# frontplatine_v0_2_140202.net
KiCad netlist of a schematic drawn in EAGLE
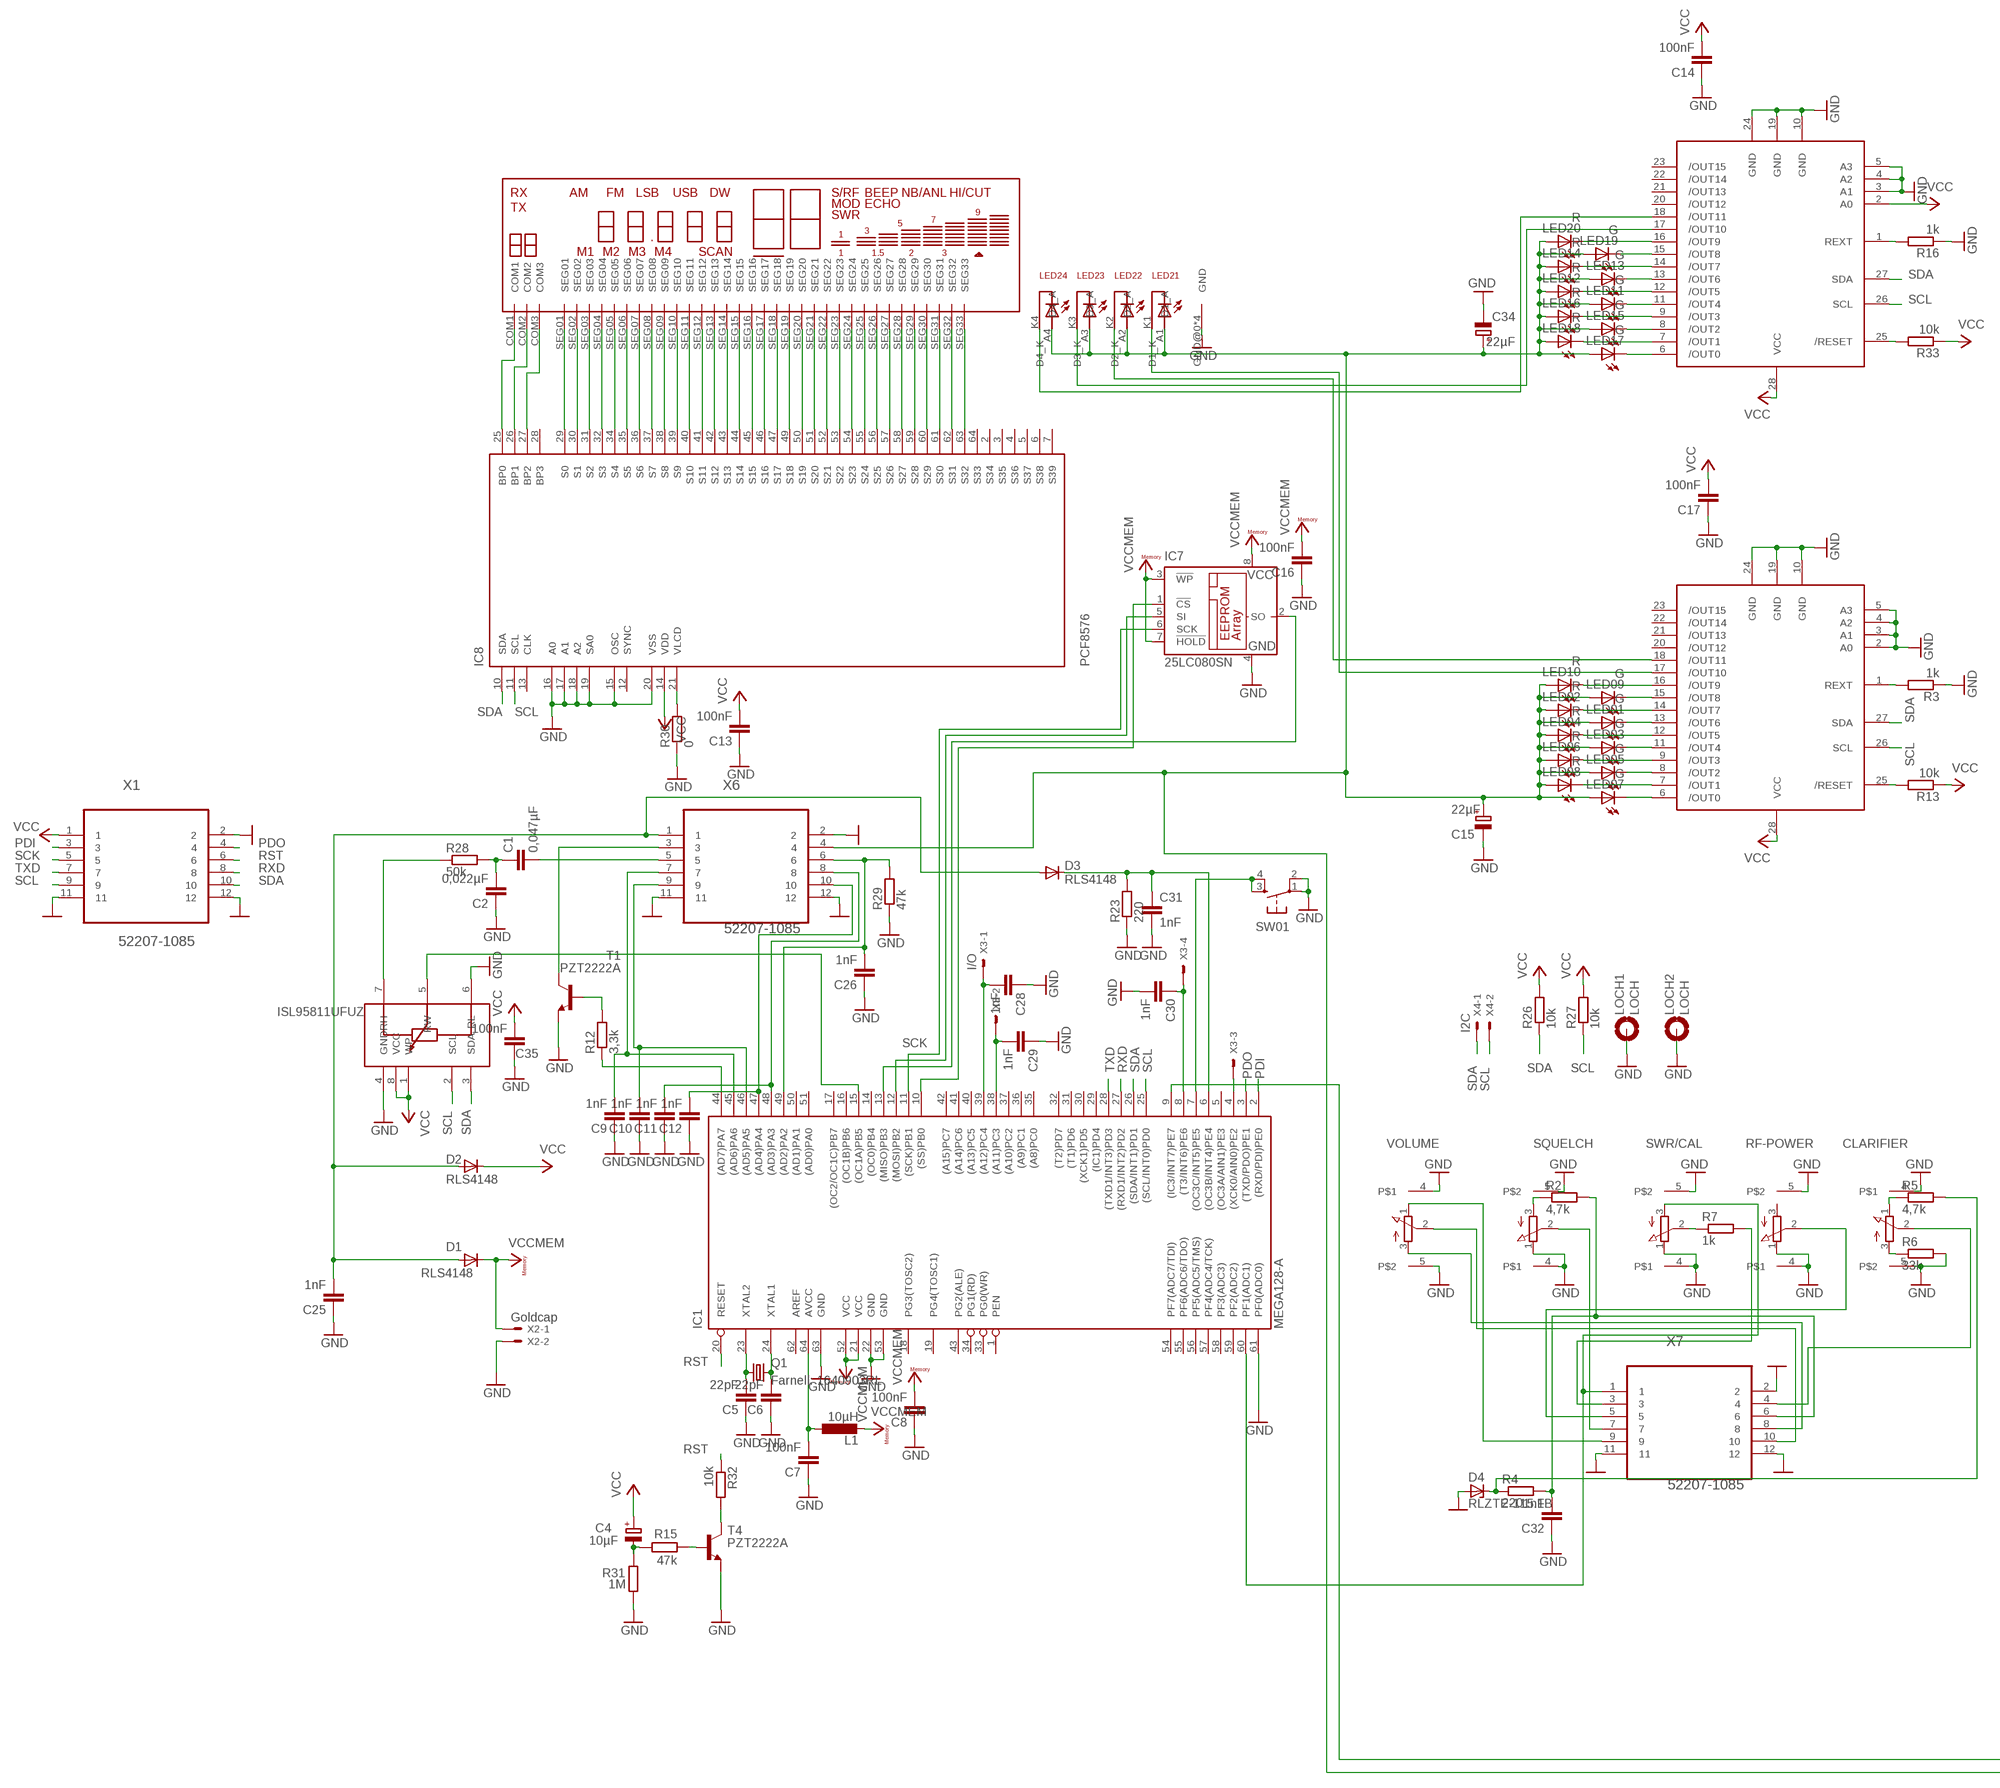
[diagram p0: schematic, sheet 1, part 1 of 2]
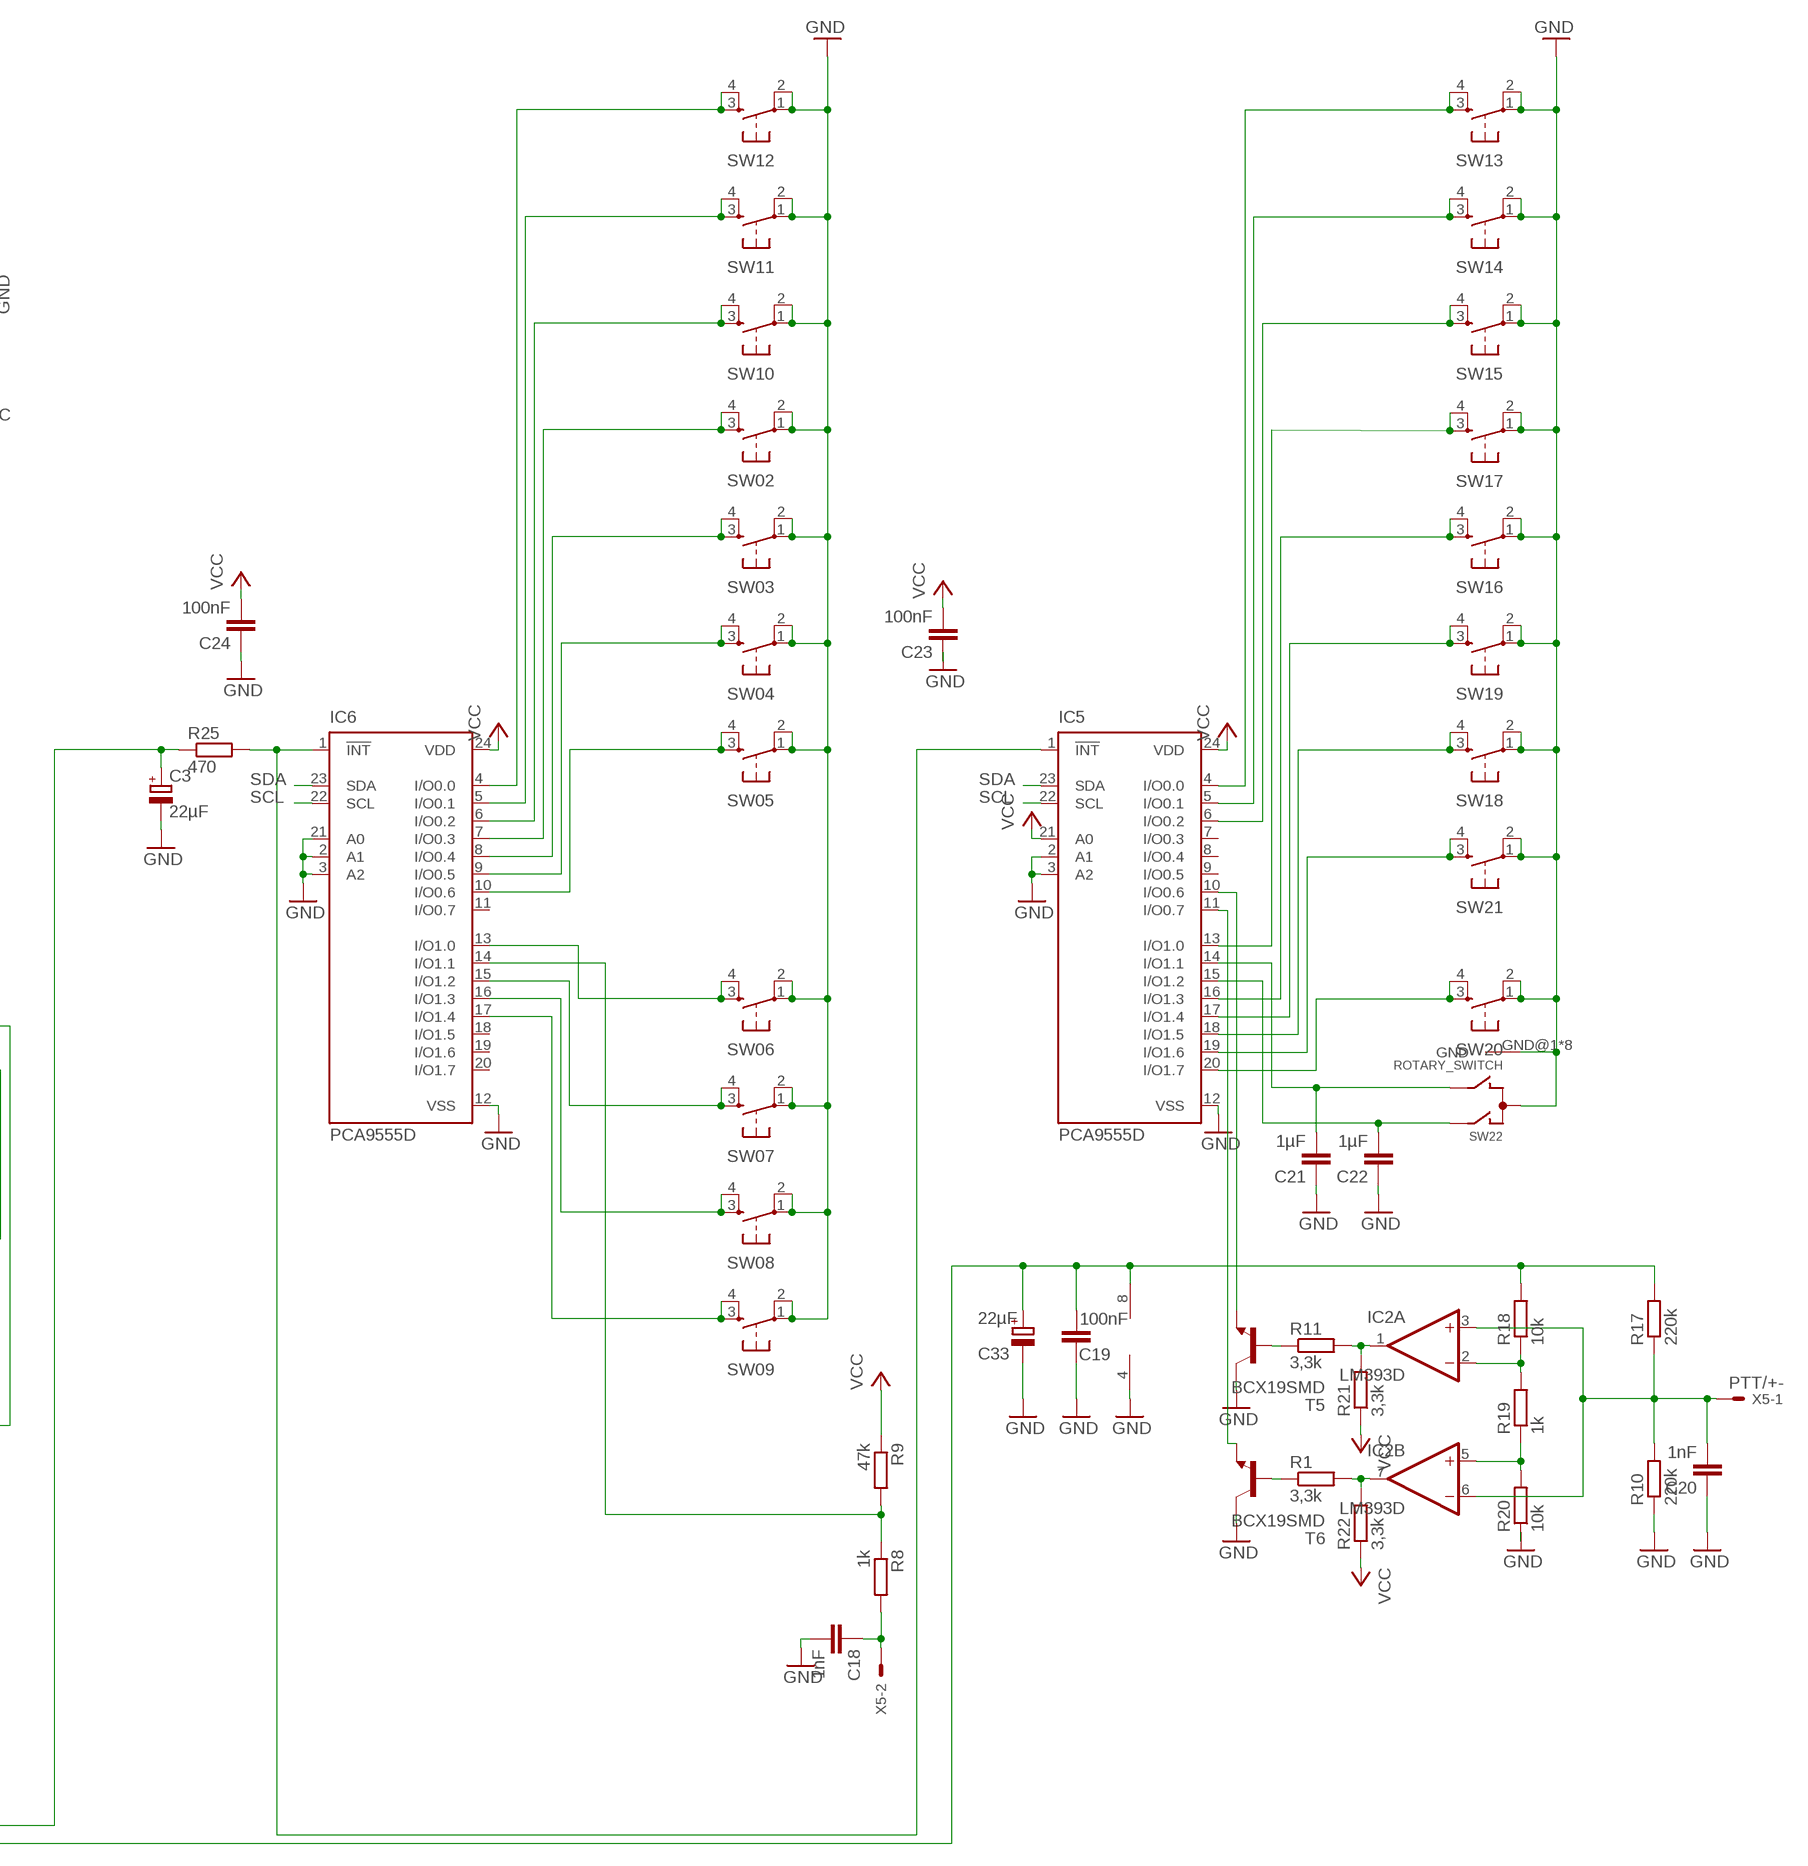
[diagram p1: schematic, sheet 1, part 2 of 2]

(export (version "E")
  (design (tool "Eeschema 10.0.6"))
  (components
    (comp (ref "C1")
      (value "0,047µF")
      (footprint "eagle-import:C1206")
      (libsource (lib "eagle-import") (part "C-EUC1206"))
    )
    (comp (ref "C2")
      (value "0,022µF")
      (footprint "eagle-import:C1206")
      (libsource (lib "eagle-import") (part "resistor_C-EUC1206"))
    )
    (comp (ref "C3")
      (value "22µF")
      (footprint "eagle-import:CT3216")
      (libsource (lib "eagle-import") (part "CPOL-EUCT3216"))
    )
    (comp (ref "C4")
      (value "10µF")
      (footprint "eagle-import:CT3216")
      (libsource (lib "eagle-import") (part "CPOL-EUCT3216"))
    )
    (comp (ref "C5")
      (value "22pF")
      (footprint "eagle-import:C1206")
      (libsource (lib "eagle-import") (part "resistor_C-EUC1206"))
    )
    (comp (ref "C6")
      (value "22pF")
      (footprint "eagle-import:C1206")
      (libsource (lib "eagle-import") (part "resistor_C-EUC1206"))
    )
    (comp (ref "C7")
      (value "100nF")
      (footprint "eagle-import:C1206")
      (libsource (lib "eagle-import") (part "resistor_C-EUC1206"))
    )
    (comp (ref "C8")
      (value "100nF")
      (footprint "eagle-import:C1206")
      (libsource (lib "eagle-import") (part "resistor_C-EUC1206"))
    )
    (comp (ref "C9")
      (value "1nF")
      (footprint "eagle-import:C1206")
      (libsource (lib "eagle-import") (part "resistor_C-EUC1206"))
    )
    (comp (ref "C10")
      (value "1nF")
      (footprint "eagle-import:C1206")
      (libsource (lib "eagle-import") (part "resistor_C-EUC1206"))
    )
    (comp (ref "C11")
      (value "1nF")
      (footprint "eagle-import:C1206")
      (libsource (lib "eagle-import") (part "resistor_C-EUC1206"))
    )
    (comp (ref "C12")
      (value "1nF")
      (footprint "eagle-import:C1206")
      (libsource (lib "eagle-import") (part "resistor_C-EUC1206"))
    )
    (comp (ref "C13")
      (value "100nF")
      (footprint "eagle-import:C1206")
      (libsource (lib "eagle-import") (part "resistor_C-EUC1206"))
    )
    (comp (ref "C14")
      (value "100nF")
      (footprint "eagle-import:C1206")
      (libsource (lib "eagle-import") (part "resistor_C-EUC1206"))
    )
    (comp (ref "C15")
      (value "22µF")
      (footprint "eagle-import:CT3216")
      (libsource (lib "eagle-import") (part "CPOL-EUCT3216"))
    )
    (comp (ref "C16")
      (value "100nF")
      (footprint "eagle-import:C1206")
      (libsource (lib "eagle-import") (part "resistor_C-EUC1206"))
    )
    (comp (ref "C17")
      (value "100nF")
      (footprint "eagle-import:C1206")
      (libsource (lib "eagle-import") (part "resistor_C-EUC1206"))
    )
    (comp (ref "C18")
      (value "1nF")
      (footprint "eagle-import:C1206")
      (libsource (lib "eagle-import") (part "resistor_C-EUC1206"))
    )
    (comp (ref "C19")
      (value "100nF")
      (footprint "eagle-import:C1206")
      (libsource (lib "eagle-import") (part "resistor_C-EUC1206"))
    )
    (comp (ref "C20")
      (value "1nF")
      (footprint "eagle-import:C1206")
      (libsource (lib "eagle-import") (part "resistor_C-EUC1206"))
    )
    (comp (ref "C21")
      (value "1µF")
      (footprint "eagle-import:C1206")
      (libsource (lib "eagle-import") (part "resistor_C-EUC1206"))
    )
    (comp (ref "C22")
      (value "1µF")
      (footprint "eagle-import:C1206")
      (libsource (lib "eagle-import") (part "resistor_C-EUC1206"))
    )
    (comp (ref "C23")
      (value "100nF")
      (footprint "eagle-import:C1206")
      (libsource (lib "eagle-import") (part "resistor_C-EUC1206"))
    )
    (comp (ref "C24")
      (value "100nF")
      (footprint "eagle-import:C1206")
      (libsource (lib "eagle-import") (part "resistor_C-EUC1206"))
    )
    (comp (ref "C25")
      (value "1nF")
      (footprint "eagle-import:C1206")
      (libsource (lib "eagle-import") (part "resistor_C-EUC1206"))
    )
    (comp (ref "C26")
      (value "1nF")
      (footprint "eagle-import:C1206")
      (libsource (lib "eagle-import") (part "resistor_C-EUC1206"))
    )
    (comp (ref "C28")
      (value "1nF")
      (footprint "eagle-import:C1206")
      (libsource (lib "eagle-import") (part "resistor_C-EUC1206"))
    )
    (comp (ref "C29")
      (value "1nF")
      (footprint "eagle-import:C1206")
      (libsource (lib "eagle-import") (part "resistor_C-EUC1206"))
    )
    (comp (ref "C30")
      (value "1nF")
      (footprint "eagle-import:C1206")
      (libsource (lib "eagle-import") (part "resistor_C-EUC1206"))
    )
    (comp (ref "C31")
      (value "1nF")
      (footprint "eagle-import:C1206")
      (libsource (lib "eagle-import") (part "resistor_C-EUC1206"))
    )
    (comp (ref "C32")
      (value "1nF")
      (footprint "eagle-import:C1206")
      (libsource (lib "eagle-import") (part "resistor_C-EUC1206"))
    )
    (comp (ref "C33")
      (value "22µF")
      (footprint "eagle-import:CT3216")
      (libsource (lib "eagle-import") (part "CPOL-EUCT3216"))
    )
    (comp (ref "C34")
      (value "22µF")
      (footprint "eagle-import:CT3216")
      (libsource (lib "eagle-import") (part "CPOL-EUCT3216"))
    )
    (comp (ref "C35")
      (value "100nF")
      (footprint "eagle-import:C1206")
      (libsource (lib "eagle-import") (part "resistor_C-EUC1206"))
    )
    (comp (ref "CLARIFIER")
      (value "POTI")
      (footprint "eagle-import:POTI")
      (libsource (lib "eagle-import") (part "POTI"))
    )
    (comp (ref "D1")
      (value "RLS4148")
      (footprint "eagle-import:SOD80C")
      (libsource (lib "eagle-import") (part "DIODE-SOD80C"))
    )
    (comp (ref "D2")
      (value "RLS4148")
      (footprint "eagle-import:SOD80C")
      (libsource (lib "eagle-import") (part "DIODE-SOD80C"))
    )
    (comp (ref "D3")
      (value "RLS4148")
      (footprint "eagle-import:SOD80C")
      (libsource (lib "eagle-import") (part "DIODE-SOD80C"))
    )
    (comp (ref "D4")
      (value "RLZTE-115.1B")
      (footprint "eagle-import:SOD80C")
      (libsource (lib "eagle-import") (part "ZENER-DIODESOD80C"))
    )
    (comp (ref "DISPLAY1")
      (value "DISPLAY")
      (footprint "eagle-import:DISPLAY")
      (libsource (lib "eagle-import") (part "DISPLAY"))
    )
    (comp (ref "IC1")
      (value "MEGA128-A")
      (footprint "eagle-import:TQFP64")
      (fields (field (name "MPN") "ATMEGA128-16AU"))
      (libsource (lib "eagle-import") (part "MEGA128-A"))
    )
    (comp (ref "IC2")
      (value "LM393D")
      (footprint "eagle-import:SO08")
      (libsource (lib "eagle-import") (part "LM393D"))
    )
    (comp (ref "IC3")
      (value "TLC59116")
      (footprint "eagle-import:TSSOP28")
      (libsource (lib "eagle-import") (part "TLC59116"))
    )
    (comp (ref "IC4")
      (value "TLC59116")
      (footprint "eagle-import:TSSOP28")
      (libsource (lib "eagle-import") (part "TLC59116"))
    )
    (comp (ref "IC5")
      (value "PCA9555D")
      (footprint "eagle-import:SO24")
      (fields (field (name "MPN") "PCA9555DW"))
      (libsource (lib "eagle-import") (part "PCA9555D"))
    )
    (comp (ref "IC6")
      (value "PCA9555D")
      (footprint "eagle-import:SO24")
      (fields (field (name "MPN") "PCA9555DW"))
      (libsource (lib "eagle-import") (part "PCA9555D"))
    )
    (comp (ref "IC7")
      (value "25LC080SN")
      (footprint "eagle-import:SO-08")
      (fields
        (field (name "MF") "MICROCHIP")
        (field (name "MPN") "25LC080/SN")
        (field (name "MPN_1") "25LC080/SN")
        (field (name "OC_FARNELL") "1137302")
        (field (name "OC_NEWARK") "96K4092")
      )
      (libsource (lib "eagle-import") (part "25SNLC080"))
    )
    (comp (ref "IC8")
      (value "PCF8576")
      (footprint "eagle-import:LQFP-ST-64-2")
      (libsource (lib "eagle-import") (part "PCF8576"))
    )
    (comp (ref "IC9")
      (value "ISL95811UFUZ")
      (footprint "eagle-import:MSOP8")
      (libsource (lib "eagle-import") (part "ISL95811UFUZ"))
    )
    (comp (ref "L1")
      (value "10µH")
      (footprint "eagle-import:L1812")
      (libsource (lib "eagle-import") (part "L-EUL1812"))
    )
    (comp (ref "LED01")
      (value "G")
      (footprint "eagle-import:CHIPLED_1206")
      (libsource (lib "eagle-import") (part "LEDCHIPLED_1206"))
    )
    (comp (ref "LED02")
      (value "R")
      (footprint "eagle-import:CHIPLED_1206")
      (libsource (lib "eagle-import") (part "LEDCHIPLED_1206"))
    )
    (comp (ref "LED03")
      (value "G")
      (footprint "eagle-import:CHIPLED_1206")
      (libsource (lib "eagle-import") (part "LEDCHIPLED_1206"))
    )
    (comp (ref "LED04")
      (value "R")
      (footprint "eagle-import:CHIPLED_1206")
      (libsource (lib "eagle-import") (part "LEDCHIPLED_1206"))
    )
    (comp (ref "LED05")
      (value "G")
      (footprint "eagle-import:CHIPLED_1206")
      (libsource (lib "eagle-import") (part "LEDCHIPLED_1206"))
    )
    (comp (ref "LED06")
      (value "R")
      (footprint "eagle-import:CHIPLED_1206")
      (libsource (lib "eagle-import") (part "LEDCHIPLED_1206"))
    )
    (comp (ref "LED07")
      (value "G")
      (footprint "eagle-import:CHIPLED_1206")
      (libsource (lib "eagle-import") (part "LEDCHIPLED_1206"))
    )
    (comp (ref "LED08")
      (value "R")
      (footprint "eagle-import:CHIPLED_1206")
      (libsource (lib "eagle-import") (part "LEDCHIPLED_1206"))
    )
    (comp (ref "LED09")
      (value "G")
      (footprint "eagle-import:CHIPLED_1206")
      (libsource (lib "eagle-import") (part "LEDCHIPLED_1206"))
    )
    (comp (ref "LED10")
      (value "R")
      (footprint "eagle-import:CHIPLED_1206")
      (libsource (lib "eagle-import") (part "LEDCHIPLED_1206"))
    )
    (comp (ref "LED11")
      (value "G")
      (footprint "eagle-import:CHIPLED_1206")
      (libsource (lib "eagle-import") (part "LEDCHIPLED_1206"))
    )
    (comp (ref "LED12")
      (value "R")
      (footprint "eagle-import:CHIPLED_1206")
      (libsource (lib "eagle-import") (part "LEDCHIPLED_1206"))
    )
    (comp (ref "LED13")
      (value "G")
      (footprint "eagle-import:CHIPLED_1206")
      (libsource (lib "eagle-import") (part "LEDCHIPLED_1206"))
    )
    (comp (ref "LED14")
      (value "R")
      (footprint "eagle-import:CHIPLED_1206")
      (libsource (lib "eagle-import") (part "LEDCHIPLED_1206"))
    )
    (comp (ref "LED15")
      (value "G")
      (footprint "eagle-import:CHIPLED_1206")
      (libsource (lib "eagle-import") (part "LEDCHIPLED_1206"))
    )
    (comp (ref "LED16")
      (value "R")
      (footprint "eagle-import:CHIPLED_1206")
      (libsource (lib "eagle-import") (part "LEDCHIPLED_1206"))
    )
    (comp (ref "LED17")
      (value "G")
      (footprint "eagle-import:CHIPLED_1206")
      (libsource (lib "eagle-import") (part "LEDCHIPLED_1206"))
    )
    (comp (ref "LED18")
      (value "R")
      (footprint "eagle-import:CHIPLED_1206")
      (libsource (lib "eagle-import") (part "LEDCHIPLED_1206"))
    )
    (comp (ref "LED19")
      (value "G")
      (footprint "eagle-import:CHIPLED_1206")
      (libsource (lib "eagle-import") (part "LEDCHIPLED_1206"))
    )
    (comp (ref "LED20")
      (value "R")
      (footprint "eagle-import:CHIPLED_1206")
      (libsource (lib "eagle-import") (part "LEDCHIPLED_1206"))
    )
    (comp (ref "LOCH1")
      (value "LOCH")
      (footprint "eagle-import:LOCH")
      (libsource (lib "eagle-import") (part "LOCH"))
    )
    (comp (ref "LOCH2")
      (value "LOCH")
      (footprint "eagle-import:LOCH")
      (libsource (lib "eagle-import") (part "LOCH"))
    )
    (comp (ref "Q1")
      (value "Farnell: 1640903RL")
      (footprint "eagle-import:HC49UP")
      (libsource (lib "eagle-import") (part "CRYSTALHC49UP"))
    )
    (comp (ref "R1")
      (value "3,3k")
      (footprint "eagle-import:R1206")
      (libsource (lib "eagle-import") (part "resistor_R-EU_R1206"))
    )
    (comp (ref "R2")
      (value "4,7k")
      (footprint "eagle-import:R1206")
      (libsource (lib "eagle-import") (part "resistor_R-EU_R1206"))
    )
    (comp (ref "R3")
      (value "1k")
      (footprint "eagle-import:R1206")
      (libsource (lib "eagle-import") (part "R-EU_R1206"))
    )
    (comp (ref "R4")
      (value "220")
      (footprint "eagle-import:R1206")
      (libsource (lib "eagle-import") (part "resistor_R-EU_R1206"))
    )
    (comp (ref "R5")
      (value "4,7k")
      (footprint "eagle-import:R1206")
      (libsource (lib "eagle-import") (part "resistor_R-EU_R1206"))
    )
    (comp (ref "R6")
      (value "33k")
      (footprint "eagle-import:R1206")
      (libsource (lib "eagle-import") (part "resistor_R-EU_R1206"))
    )
    (comp (ref "R7")
      (value "1k")
      (footprint "eagle-import:R1206")
      (libsource (lib "eagle-import") (part "resistor_R-EU_R1206"))
    )
    (comp (ref "R8")
      (value "1k")
      (footprint "eagle-import:R1206")
      (libsource (lib "eagle-import") (part "resistor_R-EU_R1206"))
    )
    (comp (ref "R9")
      (value "47k")
      (footprint "eagle-import:R1206")
      (libsource (lib "eagle-import") (part "resistor_R-EU_R1206"))
    )
    (comp (ref "R10")
      (value "220k")
      (footprint "eagle-import:R1206")
      (libsource (lib "eagle-import") (part "resistor_R-EU_R1206"))
    )
    (comp (ref "R11")
      (value "3,3k")
      (footprint "eagle-import:R1206")
      (libsource (lib "eagle-import") (part "resistor_R-EU_R1206"))
    )
    (comp (ref "R12")
      (value "3,3k")
      (footprint "eagle-import:R1206")
      (libsource (lib "eagle-import") (part "resistor_R-EU_R1206"))
    )
    (comp (ref "R13")
      (value "10k")
      (footprint "eagle-import:R1206")
      (libsource (lib "eagle-import") (part "resistor_R-EU_R1206"))
    )
    (comp (ref "R15")
      (value "47k")
      (footprint "eagle-import:R1206")
      (libsource (lib "eagle-import") (part "resistor_R-EU_R1206"))
    )
    (comp (ref "R16")
      (value "1k")
      (footprint "eagle-import:R1206")
      (libsource (lib "eagle-import") (part "R-EU_R1206"))
    )
    (comp (ref "R17")
      (value "220k")
      (footprint "eagle-import:R1206")
      (libsource (lib "eagle-import") (part "resistor_R-EU_R1206"))
    )
    (comp (ref "R18")
      (value "10k")
      (footprint "eagle-import:R1206")
      (libsource (lib "eagle-import") (part "resistor_R-EU_R1206"))
    )
    (comp (ref "R19")
      (value "1k")
      (footprint "eagle-import:R1206")
      (libsource (lib "eagle-import") (part "resistor_R-EU_R1206"))
    )
    (comp (ref "R20")
      (value "10k")
      (footprint "eagle-import:R1206")
      (libsource (lib "eagle-import") (part "resistor_R-EU_R1206"))
    )
    (comp (ref "R21")
      (value "3,3k")
      (footprint "eagle-import:R1206")
      (libsource (lib "eagle-import") (part "resistor_R-EU_R1206"))
    )
    (comp (ref "R22")
      (value "3,3k")
      (footprint "eagle-import:R1206")
      (libsource (lib "eagle-import") (part "resistor_R-EU_R1206"))
    )
    (comp (ref "R23")
      (value "220")
      (footprint "eagle-import:R1206")
      (libsource (lib "eagle-import") (part "resistor_R-EU_R1206"))
    )
    (comp (ref "R25")
      (value "470")
      (footprint "eagle-import:R1206")
      (libsource (lib "eagle-import") (part "resistor_R-EU_R1206"))
    )
    (comp (ref "R26")
      (value "10k")
      (footprint "eagle-import:R1206")
      (libsource (lib "eagle-import") (part "resistor_R-EU_R1206"))
    )
    (comp (ref "R27")
      (value "10k")
      (footprint "eagle-import:R1206")
      (libsource (lib "eagle-import") (part "resistor_R-EU_R1206"))
    )
    (comp (ref "R28")
      (value "50k")
      (footprint "eagle-import:R1206")
      (libsource (lib "eagle-import") (part "resistor_R-EU_R1206"))
    )
    (comp (ref "R29")
      (value "47k")
      (footprint "eagle-import:R1206")
      (libsource (lib "eagle-import") (part "resistor_R-EU_R1206"))
    )
    (comp (ref "R30")
      (value "0")
      (footprint "eagle-import:R1206")
      (libsource (lib "eagle-import") (part "resistor_R-EU_R1206"))
    )
    (comp (ref "R31")
      (value "1M")
      (footprint "eagle-import:R1206")
      (libsource (lib "eagle-import") (part "resistor_R-EU_R1206"))
    )
    (comp (ref "R32")
      (value "10k")
      (footprint "eagle-import:R1206")
      (libsource (lib "eagle-import") (part "resistor_R-EU_R1206"))
    )
    (comp (ref "R33")
      (value "10k")
      (footprint "eagle-import:R1206")
      (libsource (lib "eagle-import") (part "resistor_R-EU_R1206"))
    )
    (comp (ref "RF-POWER")
      (value "POTI")
      (footprint "eagle-import:POTI")
      (libsource (lib "eagle-import") (part "POTI"))
    )
    (comp (ref "SQUELCH")
      (value "POTI")
      (footprint "eagle-import:POTI")
      (libsource (lib "eagle-import") (part "POTI"))
    )
    (comp (ref "SW01")
      (value "TASTER")
      (footprint "eagle-import:TASTER")
      (libsource (lib "eagle-import") (part "TASTER"))
    )
    (comp (ref "SW02")
      (value "TASTER")
      (footprint "eagle-import:TASTER")
      (libsource (lib "eagle-import") (part "TASTER"))
    )
    (comp (ref "SW03")
      (value "TASTER")
      (footprint "eagle-import:TASTER")
      (libsource (lib "eagle-import") (part "TASTER"))
    )
    (comp (ref "SW04")
      (value "TASTER")
      (footprint "eagle-import:TASTER")
      (libsource (lib "eagle-import") (part "TASTER"))
    )
    (comp (ref "SW05")
      (value "TASTER")
      (footprint "eagle-import:TASTER")
      (libsource (lib "eagle-import") (part "TASTER"))
    )
    (comp (ref "SW06")
      (value "TASTER")
      (footprint "eagle-import:TASTER")
      (libsource (lib "eagle-import") (part "TASTER"))
    )
    (comp (ref "SW07")
      (value "TASTER")
      (footprint "eagle-import:TASTER")
      (libsource (lib "eagle-import") (part "TASTER"))
    )
    (comp (ref "SW08")
      (value "TASTER")
      (footprint "eagle-import:TASTER")
      (libsource (lib "eagle-import") (part "TASTER"))
    )
    (comp (ref "SW09")
      (value "TASTER")
      (footprint "eagle-import:TASTER")
      (libsource (lib "eagle-import") (part "TASTER"))
    )
    (comp (ref "SW10")
      (value "TASTER")
      (footprint "eagle-import:TASTER")
      (libsource (lib "eagle-import") (part "TASTER"))
    )
    (comp (ref "SW11")
      (value "TASTER")
      (footprint "eagle-import:TASTER")
      (libsource (lib "eagle-import") (part "TASTER"))
    )
    (comp (ref "SW12")
      (value "TASTER")
      (footprint "eagle-import:TASTER")
      (libsource (lib "eagle-import") (part "TASTER"))
    )
    (comp (ref "SW13")
      (value "TASTER")
      (footprint "eagle-import:TASTER")
      (libsource (lib "eagle-import") (part "TASTER"))
    )
    (comp (ref "SW14")
      (value "TASTER")
      (footprint "eagle-import:TASTER")
      (libsource (lib "eagle-import") (part "TASTER"))
    )
    (comp (ref "SW15")
      (value "TASTER")
      (footprint "eagle-import:TASTER")
      (libsource (lib "eagle-import") (part "TASTER"))
    )
    (comp (ref "SW16")
      (value "TASTER")
      (footprint "eagle-import:TASTER")
      (libsource (lib "eagle-import") (part "TASTER"))
    )
    (comp (ref "SW17")
      (value "TASTER")
      (footprint "eagle-import:TASTER")
      (libsource (lib "eagle-import") (part "TASTER"))
    )
    (comp (ref "SW18")
      (value "TASTER")
      (footprint "eagle-import:TASTER")
      (libsource (lib "eagle-import") (part "TASTER"))
    )
    (comp (ref "SW19")
      (value "TASTER")
      (footprint "eagle-import:TASTER")
      (libsource (lib "eagle-import") (part "TASTER"))
    )
    (comp (ref "SW20")
      (value "TASTER")
      (footprint "eagle-import:TASTER")
      (libsource (lib "eagle-import") (part "TASTER"))
    )
    (comp (ref "SW21")
      (value "TASTER")
      (footprint "eagle-import:TASTER")
      (libsource (lib "eagle-import") (part "TASTER"))
    )
    (comp (ref "SW22")
      (value "ROTARY_SWITCH")
      (footprint "eagle-import:ROTARY_SWITCH")
      (libsource (lib "eagle-import") (part "ROTARY_SWITCH"))
    )
    (comp (ref "SWR/CAL")
      (value "POTI")
      (footprint "eagle-import:POTI")
      (libsource (lib "eagle-import") (part "POTI"))
    )
    (comp (ref "T1")
      (value "PZT2222A")
      (footprint "eagle-import:SOT223")
      (libsource (lib "eagle-import") (part "-NPN-SOT223PZT2222A"))
    )
    (comp (ref "T4")
      (value "PZT2222A")
      (footprint "eagle-import:SOT223")
      (libsource (lib "eagle-import") (part "-NPN-SOT223PZT2222A"))
    )
    (comp (ref "T5")
      (value "BCX19SMD")
      (footprint "eagle-import:SOT23-BEC")
      (libsource (lib "eagle-import") (part "BCX19SMD"))
    )
    (comp (ref "T6")
      (value "BCX19SMD")
      (footprint "eagle-import:SOT23-BEC")
      (libsource (lib "eagle-import") (part "BCX19SMD"))
    )
    (comp (ref "VOLUME")
      (value "POTI")
      (footprint "eagle-import:POTI")
      (libsource (lib "eagle-import") (part "POTI"))
    )
    (comp (ref "X1")
      (value "52207-1085")
      (footprint "eagle-import:MOLEX_52207-1085")
      (libsource (lib "eagle-import") (part "52207-1085"))
    )
    (comp (ref "X2")
      (value "Goldcap")
      (footprint "eagle-import:53047-02")
      (fields (field (name "MF") "MOLEX") (field (name "MPN") "53047-0210"))
      (libsource (lib "eagle-import") (part "53?-02047"))
    )
    (comp (ref "X3")
      (value "I/O")
      (footprint "eagle-import:53047-04")
      (fields (field (name "MF") "WALDOM/MOLEX") (field (name "MPN") "53047-0410"))
      (libsource (lib "eagle-import") (part "53?-04047"))
    )
    (comp (ref "X4")
      (value "I2C")
      (footprint "eagle-import:53047-02")
      (fields
        (field (name "MF") "MOLEX")
        (field (name "MPN") "53047-0210")
        (field (name "MF_1") "MOLEX")
        (field (name "MPN_1") "53047-0210")
        (field (name "OC_FARNELL") "9733051")
        (field (name "OC_NEWARK") "57H4701")
      )
      (libsource (lib "eagle-import") (part "53?-02047"))
    )
    (comp (ref "X5")
      (value "PTT/+-")
      (footprint "eagle-import:53047-02")
      (fields
        (field (name "MF") "MOLEX")
        (field (name "MPN") "53047-0210")
        (field (name "MF_1") "MOLEX")
        (field (name "MPN_1") "53047-0210")
        (field (name "OC_FARNELL") "9733051")
        (field (name "OC_NEWARK") "57H4701")
      )
      (libsource (lib "eagle-import") (part "53?-02047"))
    )
    (comp (ref "X6")
      (value "52207-1085")
      (footprint "eagle-import:MOLEX_52207-1085")
      (fields
        (field (name "MPN") "52207-1085")
        (field (name "OC_FARNELL") "1079938")
        (field (name "OC_NEWARK") "58J9503")
        (field (name "PACKAGE") "SOCKET FPC, SMT, 1MM, 10 WAY")
      )
      (libsource (lib "eagle-import") (part "52207-1085"))
    )
    (comp (ref "X7")
      (value "52207-1085")
      (footprint "eagle-import:MOLEX_52207-1085")
      (fields
        (field (name "MPN") "52207-1085")
        (field (name "OC_FARNELL") "1079938")
        (field (name "OC_NEWARK") "58J9503")
        (field (name "PACKAGE") "SOCKET FPC, SMT, 1MM, 10 WAY")
      )
      (libsource (lib "eagle-import") (part "52207-1085"))
    )
  )
  (nets
    (net (code "1") (name "/PDI") (class "Default")
      (node (ref "IC1") (pin "2") (pinfunction "(RXD/PDI)PE0_2") (pintype "bidirectional"))
      (node (ref "X1") (pin "3") (pinfunction "3_3") (pintype "passive"))
    )
    (net (code "2") (name "/PDO") (class "Default")
      (node (ref "IC1") (pin "3") (pinfunction "(TXD/PDO)PE1_3") (pintype "bidirectional"))
      (node (ref "X1") (pin "4") (pinfunction "4_4") (pintype "passive"))
    )
    (net (code "3") (name "/RST") (class "Default")
      (node (ref "IC1") (pin "20") (pinfunction "RESET_20") (pintype "input"))
      (node (ref "R32") (pin "1") (pinfunction "1_1") (pintype "passive"))
      (node (ref "X1") (pin "6") (pinfunction "6_6") (pintype "passive"))
    )
    (net (code "4") (name "/RXD") (class "Default")
      (node (ref "IC1") (pin "27") (pinfunction "(RXD1/INT2)PD2_27") (pintype "bidirectional"))
      (node (ref "X1") (pin "8") (pinfunction "8_8") (pintype "passive"))
    )
    (net (code "5") (name "/SCK") (class "Default")
      (node (ref "IC1") (pin "11") (pinfunction "(SCK)PB1_11") (pintype "bidirectional"))
      (node (ref "IC7") (pin "6") (pinfunction "SCK_6") (pintype "input"))
      (node (ref "X1") (pin "5") (pinfunction "5_5") (pintype "passive"))
    )
    (net (code "6") (name "/SCL") (class "Default")
      (node (ref "IC1") (pin "25") (pinfunction "(SCL/INT0)PD0_25") (pintype "bidirectional"))
      (node (ref "IC3") (pin "26") (pinfunction "SCL_26") (pintype "bidirectional"))
      (node (ref "IC4") (pin "26") (pinfunction "SCL_26") (pintype "bidirectional"))
      (node (ref "IC5") (pin "22") (pinfunction "SCL_22") (pintype "input"))
      (node (ref "IC6") (pin "22") (pinfunction "SCL_22") (pintype "input"))
      (node (ref "IC8") (pin "11") (pinfunction "SCL_11") (pintype "input"))
      (node (ref "IC9") (pin "2") (pinfunction "SCL_2") (pintype "bidirectional"))
      (node (ref "R27") (pin "1") (pinfunction "1_1") (pintype "passive"))
      (node (ref "X1") (pin "9") (pinfunction "9_9") (pintype "passive"))
      (node (ref "X4") (pin "2") (pinfunction "S_2") (pintype "passive"))
    )
    (net (code "7") (name "/SDA") (class "Default")
      (node (ref "IC1") (pin "26") (pinfunction "(SDA/INT1)PD1_26") (pintype "bidirectional"))
      (node (ref "IC3") (pin "27") (pinfunction "SDA_27") (pintype "bidirectional"))
      (node (ref "IC4") (pin "27") (pinfunction "SDA_27") (pintype "bidirectional"))
      (node (ref "IC5") (pin "23") (pinfunction "SDA_23") (pintype "bidirectional"))
      (node (ref "IC6") (pin "23") (pinfunction "SDA_23") (pintype "bidirectional"))
      (node (ref "IC8") (pin "10") (pinfunction "SDA_10") (pintype "bidirectional"))
      (node (ref "IC9") (pin "3") (pinfunction "SDA_3") (pintype "input"))
      (node (ref "R26") (pin "1") (pinfunction "1_1") (pintype "passive"))
      (node (ref "X1") (pin "10") (pinfunction "10_10") (pintype "passive"))
      (node (ref "X4") (pin "1") (pinfunction "S_1") (pintype "passive"))
    )
    (net (code "8") (name "/TXD") (class "Default")
      (node (ref "IC1") (pin "28") (pinfunction "(TXD1/INT3)PD3_28") (pintype "bidirectional"))
      (node (ref "X1") (pin "7") (pinfunction "7_7") (pintype "passive"))
    )
    (net (code "9") (name "GND") (class "Default")
      (node (ref "C10") (pin "1") (pinfunction "1_1") (pintype "passive"))
      (node (ref "C11") (pin "1") (pinfunction "1_1") (pintype "passive"))
      (node (ref "C12") (pin "1") (pinfunction "1_1") (pintype "passive"))
      (node (ref "C13") (pin "1") (pinfunction "1_1") (pintype "passive"))
      (node (ref "C14") (pin "1") (pinfunction "1_1") (pintype "passive"))
      (node (ref "C15") (pin "-") (pinfunction "-_-") (pintype "passive"))
      (node (ref "C16") (pin "1") (pinfunction "1_1") (pintype "passive"))
      (node (ref "C17") (pin "1") (pinfunction "1_1") (pintype "passive"))
      (node (ref "C18") (pin "2") (pinfunction "2_2") (pintype "passive"))
      (node (ref "C19") (pin "1") (pinfunction "1_1") (pintype "passive"))
      (node (ref "C2") (pin "1") (pinfunction "1_1") (pintype "passive"))
      (node (ref "C20") (pin "1") (pinfunction "1_1") (pintype "passive"))
      (node (ref "C21") (pin "1") (pinfunction "1_1") (pintype "passive"))
      (node (ref "C22") (pin "1") (pinfunction "1_1") (pintype "passive"))
      (node (ref "C23") (pin "1") (pinfunction "1_1") (pintype "passive"))
      (node (ref "C24") (pin "1") (pinfunction "1_1") (pintype "passive"))
      (node (ref "C25") (pin "1") (pinfunction "1_1") (pintype "passive"))
      (node (ref "C26") (pin "1") (pinfunction "1_1") (pintype "passive"))
      (node (ref "C28") (pin "1") (pinfunction "1_1") (pintype "passive"))
      (node (ref "C29") (pin "1") (pinfunction "1_1") (pintype "passive"))
      (node (ref "C3") (pin "-") (pinfunction "-_-") (pintype "passive"))
      (node (ref "C30") (pin "2") (pinfunction "2_2") (pintype "passive"))
      (node (ref "C31") (pin "2") (pinfunction "2_2") (pintype "passive"))
      (node (ref "C32") (pin "1") (pinfunction "1_1") (pintype "passive"))
      (node (ref "C33") (pin "-") (pinfunction "-_-") (pintype "passive"))
      (node (ref "C34") (pin "-") (pinfunction "-_-") (pintype "passive"))
      (node (ref "C35") (pin "1") (pinfunction "1_1") (pintype "passive"))
      (node (ref "C5") (pin "1") (pinfunction "1_1") (pintype "passive"))
      (node (ref "C6") (pin "1") (pinfunction "1_1") (pintype "passive"))
      (node (ref "C7") (pin "1") (pinfunction "1_1") (pintype "passive"))
      (node (ref "C8") (pin "1") (pinfunction "1_1") (pintype "passive"))
      (node (ref "C9") (pin "1") (pinfunction "1_1") (pintype "passive"))
      (node (ref "CLARIFIER") (pin "4") (pinfunction "P$1_4") (pintype "power_in"))
      (node (ref "CLARIFIER") (pin "5") (pinfunction "P$2_5") (pintype "power_in"))
      (node (ref "D4") (pin "A") (pinfunction "A_A") (pintype "passive"))
      (node (ref "DISPLAY1") (pin "GND@0") (pinfunction "GND_GND@0") (pintype "power_in"))
      (node (ref "DISPLAY1") (pin "GND@3") (pinfunction "GND_GND@3") (pintype "power_in"))
      (node (ref "DISPLAY1") (pin "GND@6") (pinfunction "GND_GND@6") (pintype "power_in"))
      (node (ref "DISPLAY1") (pin "GND@7") (pinfunction "GND_GND@7") (pintype "power_in"))
      (node (ref "IC1") (pin "22") (pinfunction "GND_22") (pintype "power_in"))
      (node (ref "IC1") (pin "53") (pinfunction "GND_53") (pintype "power_in"))
      (node (ref "IC1") (pin "61") (pinfunction "PF0(ADC0)_61") (pintype "input"))
      (node (ref "IC1") (pin "63") (pinfunction "GND_63") (pintype "power_in"))
      (node (ref "IC2") (pin "4") (pinfunction "V-_4") (pintype "power_in"))
      (node (ref "IC3") (pin "10") (pinfunction "GND_10") (pintype "bidirectional"))
      (node (ref "IC3") (pin "19") (pinfunction "GND_19") (pintype "bidirectional"))
      (node (ref "IC3") (pin "2") (pinfunction "A0_2") (pintype "bidirectional"))
      (node (ref "IC3") (pin "24") (pinfunction "GND_24") (pintype "bidirectional"))
      (node (ref "IC3") (pin "3") (pinfunction "A1_3") (pintype "bidirectional"))
      (node (ref "IC3") (pin "4") (pinfunction "A2_4") (pintype "bidirectional"))
      (node (ref "IC3") (pin "5") (pinfunction "A3_5") (pintype "bidirectional"))
      (node (ref "IC4") (pin "10") (pinfunction "GND_10") (pintype "bidirectional"))
      (node (ref "IC4") (pin "19") (pinfunction "GND_19") (pintype "bidirectional"))
      (node (ref "IC4") (pin "24") (pinfunction "GND_24") (pintype "bidirectional"))
      (node (ref "IC4") (pin "3") (pinfunction "A1_3") (pintype "bidirectional"))
      (node (ref "IC4") (pin "4") (pinfunction "A2_4") (pintype "bidirectional"))
      (node (ref "IC4") (pin "5") (pinfunction "A3_5") (pintype "bidirectional"))
      (node (ref "IC5") (pin "12") (pinfunction "VSS_12") (pintype "power_in"))
      (node (ref "IC5") (pin "2") (pinfunction "A1_2") (pintype "input"))
      (node (ref "IC5") (pin "3") (pinfunction "A2_3") (pintype "input"))
      (node (ref "IC6") (pin "12") (pinfunction "VSS_12") (pintype "power_in"))
      (node (ref "IC6") (pin "2") (pinfunction "A1_2") (pintype "input"))
      (node (ref "IC6") (pin "21") (pinfunction "A0_21") (pintype "input"))
      (node (ref "IC6") (pin "3") (pinfunction "A2_3") (pintype "input"))
      (node (ref "IC7") (pin "4") (pinfunction "GND_4") (pintype "power_in"))
      (node (ref "IC8") (pin "15") (pinfunction "OSC_15") (pintype "input"))
      (node (ref "IC8") (pin "16") (pinfunction "A0_16") (pintype "input"))
      (node (ref "IC8") (pin "17") (pinfunction "A1_17") (pintype "input"))
      (node (ref "IC8") (pin "18") (pinfunction "A2_18") (pintype "input"))
      (node (ref "IC8") (pin "19") (pinfunction "SA0_19") (pintype "input"))
      (node (ref "IC8") (pin "20") (pinfunction "VSS_20") (pintype "power_in"))
      (node (ref "IC9") (pin "4") (pinfunction "GND_4") (pintype "power_in"))
      (node (ref "IC9") (pin "6") (pinfunction "RL_6") (pintype "bidirectional"))
      (node (ref "LOCH1") (pin "B3,0") (pinfunction "MOUNT_B3,0") (pintype "passive"))
      (node (ref "LOCH2") (pin "B3,0") (pinfunction "MOUNT_B3,0") (pintype "passive"))
      (node (ref "R10") (pin "1") (pinfunction "1_1") (pintype "passive"))
      (node (ref "R16") (pin "1") (pinfunction "1_1") (pintype "passive"))
      (node (ref "R20") (pin "1") (pinfunction "1_1") (pintype "passive"))
      (node (ref "R23") (pin "1") (pinfunction "1_1") (pintype "passive"))
      (node (ref "R29") (pin "1") (pinfunction "1_1") (pintype "passive"))
      (node (ref "R3") (pin "1") (pinfunction "1_1") (pintype "passive"))
      (node (ref "R30") (pin "1") (pinfunction "1_1") (pintype "passive"))
      (node (ref "R31") (pin "2") (pinfunction "2_2") (pintype "passive"))
      (node (ref "R6") (pin "2") (pinfunction "2_2") (pintype "passive"))
      (node (ref "RF-POWER") (pin "1") (pinfunction "E_1") (pintype "passive"))
      (node (ref "RF-POWER") (pin "4") (pinfunction "P$1_4") (pintype "power_in"))
      (node (ref "RF-POWER") (pin "5") (pinfunction "P$2_5") (pintype "power_in"))
      (node (ref "SQUELCH") (pin "1") (pinfunction "E_1") (pintype "passive"))
      (node (ref "SQUELCH") (pin "4") (pinfunction "P$1_4") (pintype "power_in"))
      (node (ref "SQUELCH") (pin "5") (pinfunction "P$2_5") (pintype "power_in"))
      (node (ref "SW01") (pin "1") (pinfunction "1_1") (pintype "passive"))
      (node (ref "SW01") (pin "2") (pinfunction "2_2") (pintype "passive"))
      (node (ref "SW02") (pin "1") (pinfunction "1_1") (pintype "passive"))
      (node (ref "SW02") (pin "2") (pinfunction "2_2") (pintype "passive"))
      (node (ref "SW03") (pin "1") (pinfunction "1_1") (pintype "passive"))
      (node (ref "SW03") (pin "2") (pinfunction "2_2") (pintype "passive"))
      (node (ref "SW04") (pin "1") (pinfunction "1_1") (pintype "passive"))
      (node (ref "SW04") (pin "2") (pinfunction "2_2") (pintype "passive"))
      (node (ref "SW05") (pin "1") (pinfunction "1_1") (pintype "passive"))
      (node (ref "SW05") (pin "2") (pinfunction "2_2") (pintype "passive"))
      (node (ref "SW06") (pin "1") (pinfunction "1_1") (pintype "passive"))
      (node (ref "SW06") (pin "2") (pinfunction "2_2") (pintype "passive"))
      (node (ref "SW07") (pin "1") (pinfunction "1_1") (pintype "passive"))
      (node (ref "SW07") (pin "2") (pinfunction "2_2") (pintype "passive"))
      (node (ref "SW08") (pin "1") (pinfunction "1_1") (pintype "passive"))
      (node (ref "SW08") (pin "2") (pinfunction "2_2") (pintype "passive"))
      (node (ref "SW09") (pin "1") (pinfunction "1_1") (pintype "passive"))
      (node (ref "SW09") (pin "2") (pinfunction "2_2") (pintype "passive"))
      (node (ref "SW10") (pin "1") (pinfunction "1_1") (pintype "passive"))
      (node (ref "SW10") (pin "2") (pinfunction "2_2") (pintype "passive"))
      (node (ref "SW11") (pin "1") (pinfunction "1_1") (pintype "passive"))
      (node (ref "SW11") (pin "2") (pinfunction "2_2") (pintype "passive"))
      (node (ref "SW12") (pin "1") (pinfunction "1_1") (pintype "passive"))
      (node (ref "SW12") (pin "2") (pinfunction "2_2") (pintype "passive"))
      (node (ref "SW13") (pin "1") (pinfunction "1_1") (pintype "passive"))
      (node (ref "SW13") (pin "2") (pinfunction "2_2") (pintype "passive"))
      (node (ref "SW14") (pin "1") (pinfunction "1_1") (pintype "passive"))
      (node (ref "SW14") (pin "2") (pinfunction "2_2") (pintype "passive"))
      (node (ref "SW15") (pin "1") (pinfunction "1_1") (pintype "passive"))
      (node (ref "SW15") (pin "2") (pinfunction "2_2") (pintype "passive"))
      (node (ref "SW16") (pin "1") (pinfunction "1_1") (pintype "passive"))
      (node (ref "SW16") (pin "2") (pinfunction "2_2") (pintype "passive"))
      (node (ref "SW17") (pin "1") (pinfunction "1_1") (pintype "passive"))
      (node (ref "SW17") (pin "2") (pinfunction "2_2") (pintype "passive"))
      (node (ref "SW18") (pin "1") (pinfunction "1_1") (pintype "passive"))
      (node (ref "SW18") (pin "2") (pinfunction "2_2") (pintype "passive"))
      (node (ref "SW19") (pin "1") (pinfunction "1_1") (pintype "passive"))
      (node (ref "SW19") (pin "2") (pinfunction "2_2") (pintype "passive"))
      (node (ref "SW20") (pin "1") (pinfunction "1_1") (pintype "passive"))
      (node (ref "SW20") (pin "2") (pinfunction "2_2") (pintype "passive"))
      (node (ref "SW21") (pin "1") (pinfunction "1_1") (pintype "passive"))
      (node (ref "SW21") (pin "2") (pinfunction "2_2") (pintype "passive"))
      (node (ref "SW22") (pin "C") (pinfunction "C_C") (pintype "passive"))
      (node (ref "SW22") (pin "GND@1") (pinfunction "GND_GND@1") (pintype "power_in"))
      (node (ref "SW22") (pin "GND@2") (pinfunction "GND_GND@2") (pintype "power_in"))
      (node (ref "SW22") (pin "GND@3") (pinfunction "GND_GND@3") (pintype "power_in"))
      (node (ref "SW22") (pin "GND@4") (pinfunction "GND_GND@4") (pintype "power_in"))
      (node (ref "SW22") (pin "GND@5") (pinfunction "GND_GND@5") (pintype "power_in"))
      (node (ref "SW22") (pin "GND@6") (pinfunction "GND_GND@6") (pintype "power_in"))
      (node (ref "SW22") (pin "GND@7") (pinfunction "GND_GND@7") (pintype "power_in"))
      (node (ref "SW22") (pin "GND@8") (pinfunction "GND_GND@8") (pintype "power_in"))
      (node (ref "SWR/CAL") (pin "1") (pinfunction "E_1") (pintype "passive"))
      (node (ref "SWR/CAL") (pin "4") (pinfunction "P$1_4") (pintype "power_in"))
      (node (ref "SWR/CAL") (pin "5") (pinfunction "P$2_5") (pintype "power_in"))
      (node (ref "T1") (pin "3") (pinfunction "E_3") (pintype "passive"))
      (node (ref "T4") (pin "3") (pinfunction "E_3") (pintype "passive"))
      (node (ref "T5") (pin "C") (pinfunction "C_C") (pintype "passive"))
      (node (ref "T6") (pin "C") (pinfunction "C_C") (pintype "passive"))
      (node (ref "VOLUME") (pin "4") (pinfunction "P$1_4") (pintype "power_in"))
      (node (ref "VOLUME") (pin "5") (pinfunction "P$2_5") (pintype "power_in"))
      (node (ref "X1") (pin "11") (pinfunction "11_11") (pintype "passive"))
      (node (ref "X1") (pin "12") (pinfunction "12_12") (pintype "passive"))
      (node (ref "X1") (pin "2") (pinfunction "2_2") (pintype "passive"))
      (node (ref "X2") (pin "2") (pinfunction "S_2") (pintype "passive"))
      (node (ref "X6") (pin "11") (pinfunction "11_11") (pintype "passive"))
      (node (ref "X6") (pin "12") (pinfunction "12_12") (pintype "passive"))
      (node (ref "X6") (pin "2") (pinfunction "2_2") (pintype "passive"))
      (node (ref "X7") (pin "11") (pinfunction "11_11") (pintype "passive"))
      (node (ref "X7") (pin "12") (pinfunction "12_12") (pintype "passive"))
      (node (ref "X7") (pin "2") (pinfunction "2_2") (pintype "passive"))
    )
    (net (code "10") (name "Net-(C1-Pad1)") (class "Default")
      (node (ref "C1") (pin "1") (pinfunction "1_1") (pintype "passive"))
      (node (ref "C2") (pin "2") (pinfunction "2_2") (pintype "passive"))
      (node (ref "R28") (pin "2") (pinfunction "2_2") (pintype "passive"))
    )
    (net (code "11") (name "Net-(C1-Pad2)") (class "Default")
      (node (ref "C1") (pin "2") (pinfunction "2_2") (pintype "passive"))
      (node (ref "X6") (pin "5") (pinfunction "5_5") (pintype "passive"))
    )
    (net (code "12") (name "Net-(C4-Pad-)") (class "Default")
      (node (ref "C4") (pin "-") (pinfunction "-_-") (pintype "passive"))
      (node (ref "R15") (pin "2") (pinfunction "2_2") (pintype "passive"))
      (node (ref "R31") (pin "1") (pinfunction "1_1") (pintype "passive"))
    )
    (net (code "13") (name "Net-(C25-Pad2)") (class "Default")
      (node (ref "C25") (pin "2") (pinfunction "2_2") (pintype "passive"))
      (node (ref "D1") (pin "A") (pinfunction "A_A") (pintype "passive"))
      (node (ref "D2") (pin "A") (pinfunction "A_A") (pintype "passive"))
      (node (ref "D3") (pin "A") (pinfunction "A_A") (pintype "passive"))
      (node (ref "X6") (pin "1") (pinfunction "1_1") (pintype "passive"))
    )
    (net (code "14") (name "Net-(C32-Pad2)") (class "Default")
      (node (ref "C32") (pin "2") (pinfunction "2_2") (pintype "passive"))
      (node (ref "R2") (pin "2") (pinfunction "2_2") (pintype "passive"))
      (node (ref "R4") (pin "2") (pinfunction "2_2") (pintype "passive"))
      (node (ref "X7") (pin "6") (pinfunction "6_6") (pintype "passive"))
    )
    (net (code "15") (name "Net-(CLARIFIER-A)") (class "Default")
      (node (ref "CLARIFIER") (pin "3") (pinfunction "A_3") (pintype "passive"))
      (node (ref "R6") (pin "1") (pinfunction "1_1") (pintype "passive"))
    )
    (net (code "16") (name "Net-(CLARIFIER-E)") (class "Default")
      (node (ref "CLARIFIER") (pin "1") (pinfunction "E_1") (pintype "passive"))
      (node (ref "R5") (pin "1") (pinfunction "1_1") (pintype "passive"))
    )
    (net (code "17") (name "Net-(CLARIFIER-S)") (class "Default")
      (node (ref "CLARIFIER") (pin "2") (pinfunction "S_2") (pintype "passive"))
      (node (ref "X7") (pin "4") (pinfunction "4_4") (pintype "passive"))
    )
    (net (code "18") (name "Net-(D4-PadC)") (class "Default")
      (node (ref "D4") (pin "C") (pinfunction "C_C") (pintype "passive"))
      (node (ref "R4") (pin "1") (pinfunction "1_1") (pintype "passive"))
      (node (ref "R5") (pin "2") (pinfunction "2_2") (pintype "passive"))
    )
    (net (code "19") (name "Net-(DISPLAY1-D1_A)") (class "Default")
      (node (ref "C15") (pin "+") (pinfunction "+_+") (pintype "passive"))
      (node (ref "C19") (pin "2") (pinfunction "2_2") (pintype "passive"))
      (node (ref "C33") (pin "+") (pinfunction "+_+") (pintype "passive"))
      (node (ref "C34") (pin "+") (pinfunction "+_+") (pintype "passive"))
      (node (ref "DISPLAY1") (pin "A1") (pinfunction "D1_A_A1") (pintype "input"))
      (node (ref "DISPLAY1") (pin "A2") (pinfunction "D2_A_A2") (pintype "input"))
      (node (ref "DISPLAY1") (pin "A3") (pinfunction "D3_A_A3") (pintype "input"))
      (node (ref "DISPLAY1") (pin "A4") (pinfunction "D4_A_A4") (pintype "input"))
      (node (ref "IC2") (pin "8") (pinfunction "V+_8") (pintype "power_in"))
      (node (ref "LED01") (pin "A") (pinfunction "A_A") (pintype "passive"))
      (node (ref "LED02") (pin "A") (pinfunction "A_A") (pintype "passive"))
      (node (ref "LED03") (pin "A") (pinfunction "A_A") (pintype "passive"))
      (node (ref "LED04") (pin "A") (pinfunction "A_A") (pintype "passive"))
      (node (ref "LED05") (pin "A") (pinfunction "A_A") (pintype "passive"))
      (node (ref "LED06") (pin "A") (pinfunction "A_A") (pintype "passive"))
      (node (ref "LED07") (pin "A") (pinfunction "A_A") (pintype "passive"))
      (node (ref "LED08") (pin "A") (pinfunction "A_A") (pintype "passive"))
      (node (ref "LED09") (pin "A") (pinfunction "A_A") (pintype "passive"))
      (node (ref "LED10") (pin "A") (pinfunction "A_A") (pintype "passive"))
      (node (ref "LED11") (pin "A") (pinfunction "A_A") (pintype "passive"))
      (node (ref "LED12") (pin "A") (pinfunction "A_A") (pintype "passive"))
      (node (ref "LED13") (pin "A") (pinfunction "A_A") (pintype "passive"))
      (node (ref "LED14") (pin "A") (pinfunction "A_A") (pintype "passive"))
      (node (ref "LED15") (pin "A") (pinfunction "A_A") (pintype "passive"))
      (node (ref "LED16") (pin "A") (pinfunction "A_A") (pintype "passive"))
      (node (ref "LED17") (pin "A") (pinfunction "A_A") (pintype "passive"))
      (node (ref "LED18") (pin "A") (pinfunction "A_A") (pintype "passive"))
      (node (ref "LED19") (pin "A") (pinfunction "A_A") (pintype "passive"))
      (node (ref "LED20") (pin "A") (pinfunction "A_A") (pintype "passive"))
      (node (ref "R17") (pin "2") (pinfunction "2_2") (pintype "passive"))
      (node (ref "R18") (pin "2") (pinfunction "2_2") (pintype "passive"))
      (node (ref "X6") (pin "4") (pinfunction "4_4") (pintype "passive"))
    )
    (net (code "20") (name "Net-(DISPLAY1-D1_K)") (class "Default")
      (node (ref "DISPLAY1") (pin "K1") (pinfunction "D1_K_K1") (pintype "input"))
      (node (ref "IC3") (pin "17") (pinfunction "/OUT10_17") (pintype "bidirectional"))
    )
    (net (code "21") (name "Net-(DISPLAY1-D2_K)") (class "Default")
      (node (ref "DISPLAY1") (pin "K2") (pinfunction "D2_K_K2") (pintype "input"))
      (node (ref "IC3") (pin "18") (pinfunction "/OUT11_18") (pintype "bidirectional"))
    )
    (net (code "22") (name "Net-(DISPLAY1-D3_K)") (class "Default")
      (node (ref "DISPLAY1") (pin "K3") (pinfunction "D3_K_K3") (pintype "input"))
      (node (ref "IC4") (pin "17") (pinfunction "/OUT10_17") (pintype "bidirectional"))
    )
    (net (code "23") (name "Net-(DISPLAY1-D4_K)") (class "Default")
      (node (ref "DISPLAY1") (pin "K4") (pinfunction "D4_K_K4") (pintype "input"))
      (node (ref "IC4") (pin "18") (pinfunction "/OUT11_18") (pintype "bidirectional"))
    )
    (net (code "24") (name "Net-(IC1-(A11)PC3)") (class "Default")
      (node (ref "C29") (pin "2") (pinfunction "2_2") (pintype "passive"))
      (node (ref "IC1") (pin "38") (pinfunction "(A11)PC3_38") (pintype "output"))
      (node (ref "X3") (pin "2") (pinfunction "S_2") (pintype "passive"))
    )
    (net (code "25") (name "Net-(IC1-(A12)PC4)") (class "Default")
      (node (ref "C28") (pin "2") (pinfunction "2_2") (pintype "passive"))
      (node (ref "IC1") (pin "39") (pinfunction "(A12)PC4_39") (pintype "output"))
      (node (ref "X3") (pin "1") (pinfunction "S_1") (pintype "passive"))
    )
    (net (code "26") (name "Net-(IC1-(AD2)PA2)") (class "Default")
      (node (ref "C26") (pin "2") (pinfunction "2_2") (pintype "passive"))
      (node (ref "IC1") (pin "49") (pinfunction "(AD2)PA2_49") (pintype "bidirectional"))
      (node (ref "R29") (pin "2") (pinfunction "2_2") (pintype "passive"))
      (node (ref "X6") (pin "6") (pinfunction "6_6") (pintype "passive"))
    )
    (net (code "27") (name "Net-(IC1-(AD3)PA3)") (class "Default")
      (node (ref "C11") (pin "2") (pinfunction "2_2") (pintype "passive"))
      (node (ref "IC1") (pin "48") (pinfunction "(AD3)PA3_48") (pintype "bidirectional"))
      (node (ref "X6") (pin "8") (pinfunction "8_8") (pintype "passive"))
    )
    (net (code "28") (name "Net-(IC1-(AD4)PA4)") (class "Default")
      (node (ref "C12") (pin "2") (pinfunction "2_2") (pintype "passive"))
      (node (ref "IC1") (pin "47") (pinfunction "(AD4)PA4_47") (pintype "bidirectional"))
      (node (ref "X6") (pin "10") (pinfunction "10_10") (pintype "passive"))
    )
    (net (code "29") (name "Net-(IC1-(AD5)PA5)") (class "Default")
      (node (ref "C10") (pin "2") (pinfunction "2_2") (pintype "passive"))
      (node (ref "IC1") (pin "46") (pinfunction "(AD5)PA5_46") (pintype "bidirectional"))
      (node (ref "X6") (pin "9") (pinfunction "9_9") (pintype "passive"))
    )
    (net (code "30") (name "Net-(IC1-(AD6)PA6)") (class "Default")
      (node (ref "C9") (pin "2") (pinfunction "2_2") (pintype "passive"))
      (node (ref "IC1") (pin "45") (pinfunction "(AD6)PA6_45") (pintype "bidirectional"))
      (node (ref "X6") (pin "7") (pinfunction "7_7") (pintype "passive"))
    )
    (net (code "31") (name "Net-(IC1-(AD7)PA7)") (class "Default")
      (node (ref "IC1") (pin "44") (pinfunction "(AD7)PA7_44") (pintype "bidirectional"))
      (node (ref "R12") (pin "1") (pinfunction "1_1") (pintype "passive"))
    )
    (net (code "32") (name "Net-(IC1-(IC3{slash}INT7)PE7)") (class "Default")
      (node (ref "C3") (pin "+") (pinfunction "+_+") (pintype "passive"))
      (node (ref "IC1") (pin "9") (pinfunction "(IC3/INT7)PE7_9") (pintype "bidirectional"))
      (node (ref "R25") (pin "1") (pinfunction "1_1") (pintype "passive"))
    )
    (net (code "33") (name "Net-(IC1-(MISO)PB3)") (class "Default")
      (node (ref "IC1") (pin "13") (pinfunction "(MISO)PB3_13") (pintype "bidirectional"))
      (node (ref "IC7") (pin "2") (pinfunction "SO_2") (pintype "bidirectional"))
    )
    (net (code "34") (name "Net-(IC1-(MOSI)PB2)") (class "Default")
      (node (ref "IC1") (pin "12") (pinfunction "(MOSI)PB2_12") (pintype "bidirectional"))
      (node (ref "IC7") (pin "5") (pinfunction "SI_5") (pintype "input"))
    )
    (net (code "35") (name "Net-(IC1-(OC1A)PB5)") (class "Default")
      (node (ref "IC1") (pin "15") (pinfunction "(OC1A)PB5_15") (pintype "bidirectional"))
      (node (ref "IC9") (pin "5") (pinfunction "RW_5") (pintype "bidirectional"))
    )
    (net (code "36") (name "Net-(IC1-(OC3B{slash}INT4)PE4)") (class "Default")
      (node (ref "C31") (pin "1") (pinfunction "1_1") (pintype "passive"))
      (node (ref "D3") (pin "C") (pinfunction "C_C") (pintype "passive"))
      (node (ref "IC1") (pin "6") (pinfunction "(OC3B/INT4)PE4_6") (pintype "bidirectional"))
      (node (ref "R23") (pin "2") (pinfunction "2_2") (pintype "passive"))
    )
    (net (code "37") (name "Net-(IC1-(OC3C{slash}INT5)PE5)") (class "Default")
      (node (ref "IC1") (pin "7") (pinfunction "(OC3C/INT5)PE5_7") (pintype "bidirectional"))
      (node (ref "SW01") (pin "3") (pinfunction "3_3") (pintype "passive"))
      (node (ref "SW01") (pin "4") (pinfunction "4_4") (pintype "passive"))
    )
    (net (code "38") (name "Net-(IC1-(SS)PB0)") (class "Default")
      (node (ref "IC1") (pin "10") (pinfunction "(SS)PB0_10") (pintype "bidirectional"))
      (node (ref "IC7") (pin "1") (pinfunction "~{CS}_1") (pintype "input"))
    )
    (net (code "39") (name "Net-(IC1-(T3{slash}INT6)PE6)") (class "Default")
      (node (ref "C30") (pin "1") (pinfunction "1_1") (pintype "passive"))
      (node (ref "IC1") (pin "8") (pinfunction "(T3/INT6)PE6_8") (pintype "bidirectional"))
      (node (ref "X3") (pin "4") (pinfunction "S_4") (pintype "passive"))
    )
    (net (code "40") (name "Net-(IC1-(XCK0{slash}AIN0)PE2)") (class "Default")
      (node (ref "IC1") (pin "4") (pinfunction "(XCK0/AIN0)PE2_4") (pintype "bidirectional"))
      (node (ref "X3") (pin "3") (pinfunction "S_3") (pintype "passive"))
    )
    (net (code "41") (name "Net-(IC1-AVCC)") (class "Default")
      (node (ref "C7") (pin "2") (pinfunction "2_2") (pintype "passive"))
      (node (ref "IC1") (pin "64") (pinfunction "AVCC_64") (pintype "power_in"))
      (node (ref "L1") (pin "1") (pinfunction "1_1") (pintype "passive"))
    )
    (net (code "42") (name "Net-(IC1-PF1(ADC1))") (class "Default")
      (node (ref "IC1") (pin "60") (pinfunction "PF1(ADC1)_60") (pintype "input"))
      (node (ref "SWR/CAL") (pin "3") (pinfunction "A_3") (pintype "passive"))
      (node (ref "X7") (pin "1") (pinfunction "1_1") (pintype "passive"))
    )
    (net (code "43") (name "Net-(IC1-XTAL1)") (class "Default")
      (node (ref "C6") (pin "2") (pinfunction "2_2") (pintype "passive"))
      (node (ref "IC1") (pin "24") (pinfunction "XTAL1_24") (pintype "bidirectional"))
      (node (ref "Q1") (pin "2") (pinfunction "2_2") (pintype "passive"))
    )
    (net (code "44") (name "Net-(IC1-XTAL2)") (class "Default")
      (node (ref "C5") (pin "2") (pinfunction "2_2") (pintype "passive"))
      (node (ref "IC1") (pin "23") (pinfunction "XTAL2_23") (pintype "bidirectional"))
      (node (ref "Q1") (pin "1") (pinfunction "1_1") (pintype "passive"))
    )
    (net (code "45") (name "Net-(IC2A-+IN)") (class "Default")
      (node (ref "C20") (pin "2") (pinfunction "2_2") (pintype "passive"))
      (node (ref "IC2") (pin "3") (pinfunction "+IN_3") (pintype "input"))
      (node (ref "IC2") (pin "6") (pinfunction "-IN_6") (pintype "input"))
      (node (ref "R10") (pin "2") (pinfunction "2_2") (pintype "passive"))
      (node (ref "R17") (pin "1") (pinfunction "1_1") (pintype "passive"))
      (node (ref "X5") (pin "1") (pinfunction "S_1") (pintype "passive"))
    )
    (net (code "46") (name "Net-(IC2A--IN)") (class "Default")
      (node (ref "IC2") (pin "2") (pinfunction "-IN_2") (pintype "input"))
      (node (ref "R18") (pin "1") (pinfunction "1_1") (pintype "passive"))
      (node (ref "R19") (pin "2") (pinfunction "2_2") (pintype "passive"))
    )
    (net (code "47") (name "Net-(IC2A-OUT)") (class "Default")
      (node (ref "IC2") (pin "1") (pinfunction "OUT_1") (pintype "output"))
      (node (ref "R11") (pin "2") (pinfunction "2_2") (pintype "passive"))
      (node (ref "R21") (pin "2") (pinfunction "2_2") (pintype "passive"))
    )
    (net (code "48") (name "Net-(IC2B-+IN)") (class "Default")
      (node (ref "IC2") (pin "5") (pinfunction "+IN_5") (pintype "input"))
      (node (ref "R19") (pin "1") (pinfunction "1_1") (pintype "passive"))
      (node (ref "R20") (pin "2") (pinfunction "2_2") (pintype "passive"))
    )
    (net (code "49") (name "Net-(IC2B-OUT)") (class "Default")
      (node (ref "IC2") (pin "7") (pinfunction "OUT_7") (pintype "output"))
      (node (ref "R1") (pin "2") (pinfunction "2_2") (pintype "passive"))
      (node (ref "R22") (pin "2") (pinfunction "2_2") (pintype "passive"))
    )
    (net (code "50") (name "Net-(IC3-REXT)") (class "Default")
      (node (ref "IC3") (pin "1") (pinfunction "REXT_1") (pintype "bidirectional"))
      (node (ref "R3") (pin "2") (pinfunction "2_2") (pintype "passive"))
    )
    (net (code "51") (name "Net-(IC3-{slash}OUT0)") (class "Default")
      (node (ref "IC3") (pin "6") (pinfunction "/OUT0_6") (pintype "bidirectional"))
      (node (ref "LED07") (pin "C") (pinfunction "C_C") (pintype "passive"))
    )
    (net (code "52") (name "Net-(IC3-{slash}OUT1)") (class "Default")
      (node (ref "IC3") (pin "7") (pinfunction "/OUT1_7") (pintype "bidirectional"))
      (node (ref "LED08") (pin "C") (pinfunction "C_C") (pintype "passive"))
    )
    (net (code "53") (name "Net-(IC3-{slash}OUT2)") (class "Default")
      (node (ref "IC3") (pin "8") (pinfunction "/OUT2_8") (pintype "bidirectional"))
      (node (ref "LED05") (pin "C") (pinfunction "C_C") (pintype "passive"))
    )
    (net (code "54") (name "Net-(IC3-{slash}OUT3)") (class "Default")
      (node (ref "IC3") (pin "9") (pinfunction "/OUT3_9") (pintype "bidirectional"))
      (node (ref "LED06") (pin "C") (pinfunction "C_C") (pintype "passive"))
    )
    (net (code "55") (name "Net-(IC3-{slash}OUT4)") (class "Default")
      (node (ref "IC3") (pin "11") (pinfunction "/OUT4_11") (pintype "bidirectional"))
      (node (ref "LED03") (pin "C") (pinfunction "C_C") (pintype "passive"))
    )
    (net (code "56") (name "Net-(IC3-{slash}OUT5)") (class "Default")
      (node (ref "IC3") (pin "12") (pinfunction "/OUT5_12") (pintype "bidirectional"))
      (node (ref "LED04") (pin "C") (pinfunction "C_C") (pintype "passive"))
    )
    (net (code "57") (name "Net-(IC3-{slash}OUT6)") (class "Default")
      (node (ref "IC3") (pin "13") (pinfunction "/OUT6_13") (pintype "bidirectional"))
      (node (ref "LED01") (pin "C") (pinfunction "C_C") (pintype "passive"))
    )
    (net (code "58") (name "Net-(IC3-{slash}OUT7)") (class "Default")
      (node (ref "IC3") (pin "14") (pinfunction "/OUT7_14") (pintype "bidirectional"))
      (node (ref "LED02") (pin "C") (pinfunction "C_C") (pintype "passive"))
    )
    (net (code "59") (name "Net-(IC3-{slash}OUT8)") (class "Default")
      (node (ref "IC3") (pin "15") (pinfunction "/OUT8_15") (pintype "bidirectional"))
      (node (ref "LED09") (pin "C") (pinfunction "C_C") (pintype "passive"))
    )
    (net (code "60") (name "Net-(IC3-{slash}OUT9)") (class "Default")
      (node (ref "IC3") (pin "16") (pinfunction "/OUT9_16") (pintype "bidirectional"))
      (node (ref "LED10") (pin "C") (pinfunction "C_C") (pintype "passive"))
    )
    (net (code "61") (name "Net-(IC3-{slash}RESET)") (class "Default")
      (node (ref "IC3") (pin "25") (pinfunction "/RESET_25") (pintype "bidirectional"))
      (node (ref "R13") (pin "2") (pinfunction "2_2") (pintype "passive"))
    )
    (net (code "62") (name "Net-(IC4-REXT)") (class "Default")
      (node (ref "IC4") (pin "1") (pinfunction "REXT_1") (pintype "bidirectional"))
      (node (ref "R16") (pin "2") (pinfunction "2_2") (pintype "passive"))
    )
    (net (code "63") (name "Net-(IC4-{slash}OUT0)") (class "Default")
      (node (ref "IC4") (pin "6") (pinfunction "/OUT0_6") (pintype "bidirectional"))
      (node (ref "LED17") (pin "C") (pinfunction "C_C") (pintype "passive"))
    )
    (net (code "64") (name "Net-(IC4-{slash}OUT1)") (class "Default")
      (node (ref "IC4") (pin "7") (pinfunction "/OUT1_7") (pintype "bidirectional"))
      (node (ref "LED18") (pin "C") (pinfunction "C_C") (pintype "passive"))
    )
    (net (code "65") (name "Net-(IC4-{slash}OUT2)") (class "Default")
      (node (ref "IC4") (pin "8") (pinfunction "/OUT2_8") (pintype "bidirectional"))
      (node (ref "LED15") (pin "C") (pinfunction "C_C") (pintype "passive"))
    )
    (net (code "66") (name "Net-(IC4-{slash}OUT3)") (class "Default")
      (node (ref "IC4") (pin "9") (pinfunction "/OUT3_9") (pintype "bidirectional"))
      (node (ref "LED16") (pin "C") (pinfunction "C_C") (pintype "passive"))
    )
    (net (code "67") (name "Net-(IC4-{slash}OUT4)") (class "Default")
      (node (ref "IC4") (pin "11") (pinfunction "/OUT4_11") (pintype "bidirectional"))
      (node (ref "LED11") (pin "C") (pinfunction "C_C") (pintype "passive"))
    )
    (net (code "68") (name "Net-(IC4-{slash}OUT5)") (class "Default")
      (node (ref "IC4") (pin "12") (pinfunction "/OUT5_12") (pintype "bidirectional"))
      (node (ref "LED12") (pin "C") (pinfunction "C_C") (pintype "passive"))
    )
    (net (code "69") (name "Net-(IC4-{slash}OUT6)") (class "Default")
      (node (ref "IC4") (pin "13") (pinfunction "/OUT6_13") (pintype "bidirectional"))
      (node (ref "LED13") (pin "C") (pinfunction "C_C") (pintype "passive"))
    )
    (net (code "70") (name "Net-(IC4-{slash}OUT7)") (class "Default")
      (node (ref "IC4") (pin "14") (pinfunction "/OUT7_14") (pintype "bidirectional"))
      (node (ref "LED14") (pin "C") (pinfunction "C_C") (pintype "passive"))
    )
    (net (code "71") (name "Net-(IC4-{slash}OUT8)") (class "Default")
      (node (ref "IC4") (pin "15") (pinfunction "/OUT8_15") (pintype "bidirectional"))
      (node (ref "LED19") (pin "C") (pinfunction "C_C") (pintype "passive"))
    )
    (net (code "72") (name "Net-(IC4-{slash}OUT9)") (class "Default")
      (node (ref "IC4") (pin "16") (pinfunction "/OUT9_16") (pintype "bidirectional"))
      (node (ref "LED20") (pin "C") (pinfunction "C_C") (pintype "passive"))
    )
    (net (code "73") (name "Net-(IC4-{slash}RESET)") (class "Default")
      (node (ref "IC4") (pin "25") (pinfunction "/RESET_25") (pintype "bidirectional"))
      (node (ref "R33") (pin "2") (pinfunction "2_2") (pintype "passive"))
    )
    (net (code "74") (name "Net-(IC5-I{slash}O0.0)") (class "Default")
      (node (ref "IC5") (pin "4") (pinfunction "I/O0.0_4") (pintype "bidirectional"))
      (node (ref "SW13") (pin "3") (pinfunction "3_3") (pintype "passive"))
      (node (ref "SW13") (pin "4") (pinfunction "4_4") (pintype "passive"))
    )
    (net (code "75") (name "Net-(IC5-I{slash}O0.1)") (class "Default")
      (node (ref "IC5") (pin "5") (pinfunction "I/O0.1_5") (pintype "bidirectional"))
      (node (ref "SW14") (pin "3") (pinfunction "3_3") (pintype "passive"))
      (node (ref "SW14") (pin "4") (pinfunction "4_4") (pintype "passive"))
    )
    (net (code "76") (name "Net-(IC5-I{slash}O0.2)") (class "Default")
      (node (ref "IC5") (pin "6") (pinfunction "I/O0.2_6") (pintype "bidirectional"))
      (node (ref "SW15") (pin "3") (pinfunction "3_3") (pintype "passive"))
      (node (ref "SW15") (pin "4") (pinfunction "4_4") (pintype "passive"))
    )
    (net (code "77") (name "Net-(IC5-I{slash}O0.6)") (class "Default")
      (node (ref "IC5") (pin "10") (pinfunction "I/O0.6_10") (pintype "bidirectional"))
      (node (ref "T5") (pin "E") (pinfunction "E_E") (pintype "passive"))
    )
    (net (code "78") (name "Net-(IC5-I{slash}O0.7)") (class "Default")
      (node (ref "IC5") (pin "11") (pinfunction "I/O0.7_11") (pintype "bidirectional"))
      (node (ref "T6") (pin "E") (pinfunction "E_E") (pintype "passive"))
    )
    (net (code "79") (name "Net-(IC5-I{slash}O1.0)") (class "Default")
      (node (ref "IC5") (pin "13") (pinfunction "I/O1.0_13") (pintype "bidirectional"))
      (node (ref "SW17") (pin "3") (pinfunction "3_3") (pintype "passive"))
      (node (ref "SW17") (pin "4") (pinfunction "4_4") (pintype "passive"))
    )
    (net (code "80") (name "Net-(IC5-I{slash}O1.1)") (class "Default")
      (node (ref "C21") (pin "2") (pinfunction "2_2") (pintype "passive"))
      (node (ref "IC5") (pin "14") (pinfunction "I/O1.1_14") (pintype "bidirectional"))
      (node (ref "SW22") (pin "B") (pinfunction "B_B") (pintype "passive"))
    )
    (net (code "81") (name "Net-(IC5-I{slash}O1.2)") (class "Default")
      (node (ref "C22") (pin "2") (pinfunction "2_2") (pintype "passive"))
      (node (ref "IC5") (pin "15") (pinfunction "I/O1.2_15") (pintype "bidirectional"))
      (node (ref "SW22") (pin "A") (pinfunction "A_A") (pintype "passive"))
    )
    (net (code "82") (name "Net-(IC5-I{slash}O1.3)") (class "Default")
      (node (ref "IC5") (pin "16") (pinfunction "I/O1.3_16") (pintype "bidirectional"))
      (node (ref "SW16") (pin "3") (pinfunction "3_3") (pintype "passive"))
      (node (ref "SW16") (pin "4") (pinfunction "4_4") (pintype "passive"))
    )
    (net (code "83") (name "Net-(IC5-I{slash}O1.4)") (class "Default")
      (node (ref "IC5") (pin "17") (pinfunction "I/O1.4_17") (pintype "bidirectional"))
      (node (ref "SW19") (pin "3") (pinfunction "3_3") (pintype "passive"))
      (node (ref "SW19") (pin "4") (pinfunction "4_4") (pintype "passive"))
    )
    (net (code "84") (name "Net-(IC5-I{slash}O1.5)") (class "Default")
      (node (ref "IC5") (pin "18") (pinfunction "I/O1.5_18") (pintype "bidirectional"))
      (node (ref "SW18") (pin "3") (pinfunction "3_3") (pintype "passive"))
      (node (ref "SW18") (pin "4") (pinfunction "4_4") (pintype "passive"))
    )
    (net (code "85") (name "Net-(IC5-I{slash}O1.6)") (class "Default")
      (node (ref "IC5") (pin "19") (pinfunction "I/O1.6_19") (pintype "bidirectional"))
      (node (ref "SW21") (pin "3") (pinfunction "3_3") (pintype "passive"))
      (node (ref "SW21") (pin "4") (pinfunction "4_4") (pintype "passive"))
    )
    (net (code "86") (name "Net-(IC5-I{slash}O1.7)") (class "Default")
      (node (ref "IC5") (pin "20") (pinfunction "I/O1.7_20") (pintype "bidirectional"))
      (node (ref "SW20") (pin "3") (pinfunction "3_3") (pintype "passive"))
      (node (ref "SW20") (pin "4") (pinfunction "4_4") (pintype "passive"))
    )
    (net (code "87") (name "Net-(IC5-~{INT})") (class "Default")
      (node (ref "IC5") (pin "1") (pinfunction "~{INT}_1") (pintype "output"))
      (node (ref "IC6") (pin "1") (pinfunction "~{INT}_1") (pintype "output"))
      (node (ref "R25") (pin "2") (pinfunction "2_2") (pintype "passive"))
    )
    (net (code "88") (name "Net-(IC6-I{slash}O0.0)") (class "Default")
      (node (ref "IC6") (pin "4") (pinfunction "I/O0.0_4") (pintype "bidirectional"))
      (node (ref "SW12") (pin "3") (pinfunction "3_3") (pintype "passive"))
      (node (ref "SW12") (pin "4") (pinfunction "4_4") (pintype "passive"))
    )
    (net (code "89") (name "Net-(IC6-I{slash}O0.1)") (class "Default")
      (node (ref "IC6") (pin "5") (pinfunction "I/O0.1_5") (pintype "bidirectional"))
      (node (ref "SW11") (pin "3") (pinfunction "3_3") (pintype "passive"))
      (node (ref "SW11") (pin "4") (pinfunction "4_4") (pintype "passive"))
    )
    (net (code "90") (name "Net-(IC6-I{slash}O0.2)") (class "Default")
      (node (ref "IC6") (pin "6") (pinfunction "I/O0.2_6") (pintype "bidirectional"))
      (node (ref "SW10") (pin "3") (pinfunction "3_3") (pintype "passive"))
      (node (ref "SW10") (pin "4") (pinfunction "4_4") (pintype "passive"))
    )
    (net (code "91") (name "Net-(IC6-I{slash}O0.3)") (class "Default")
      (node (ref "IC6") (pin "7") (pinfunction "I/O0.3_7") (pintype "bidirectional"))
      (node (ref "SW02") (pin "3") (pinfunction "3_3") (pintype "passive"))
      (node (ref "SW02") (pin "4") (pinfunction "4_4") (pintype "passive"))
    )
    (net (code "92") (name "Net-(IC6-I{slash}O0.4)") (class "Default")
      (node (ref "IC6") (pin "8") (pinfunction "I/O0.4_8") (pintype "bidirectional"))
      (node (ref "SW03") (pin "3") (pinfunction "3_3") (pintype "passive"))
      (node (ref "SW03") (pin "4") (pinfunction "4_4") (pintype "passive"))
    )
    (net (code "93") (name "Net-(IC6-I{slash}O0.5)") (class "Default")
      (node (ref "IC6") (pin "9") (pinfunction "I/O0.5_9") (pintype "bidirectional"))
      (node (ref "SW04") (pin "3") (pinfunction "3_3") (pintype "passive"))
      (node (ref "SW04") (pin "4") (pinfunction "4_4") (pintype "passive"))
    )
    (net (code "94") (name "Net-(IC6-I{slash}O0.6)") (class "Default")
      (node (ref "IC6") (pin "10") (pinfunction "I/O0.6_10") (pintype "bidirectional"))
      (node (ref "SW05") (pin "3") (pinfunction "3_3") (pintype "passive"))
      (node (ref "SW05") (pin "4") (pinfunction "4_4") (pintype "passive"))
    )
    (net (code "95") (name "Net-(IC6-I{slash}O1.0)") (class "Default")
      (node (ref "IC6") (pin "13") (pinfunction "I/O1.0_13") (pintype "bidirectional"))
      (node (ref "SW06") (pin "3") (pinfunction "3_3") (pintype "passive"))
      (node (ref "SW06") (pin "4") (pinfunction "4_4") (pintype "passive"))
    )
    (net (code "96") (name "Net-(IC6-I{slash}O1.1)") (class "Default")
      (node (ref "IC6") (pin "14") (pinfunction "I/O1.1_14") (pintype "bidirectional"))
      (node (ref "R8") (pin "1") (pinfunction "1_1") (pintype "passive"))
      (node (ref "R9") (pin "2") (pinfunction "2_2") (pintype "passive"))
    )
    (net (code "97") (name "Net-(IC6-I{slash}O1.2)") (class "Default")
      (node (ref "IC6") (pin "15") (pinfunction "I/O1.2_15") (pintype "bidirectional"))
      (node (ref "SW07") (pin "3") (pinfunction "3_3") (pintype "passive"))
      (node (ref "SW07") (pin "4") (pinfunction "4_4") (pintype "passive"))
    )
    (net (code "98") (name "Net-(IC6-I{slash}O1.3)") (class "Default")
      (node (ref "IC6") (pin "16") (pinfunction "I/O1.3_16") (pintype "bidirectional"))
      (node (ref "SW08") (pin "3") (pinfunction "3_3") (pintype "passive"))
      (node (ref "SW08") (pin "4") (pinfunction "4_4") (pintype "passive"))
    )
    (net (code "99") (name "Net-(IC6-I{slash}O1.4)") (class "Default")
      (node (ref "IC6") (pin "17") (pinfunction "I/O1.4_17") (pintype "bidirectional"))
      (node (ref "SW09") (pin "3") (pinfunction "3_3") (pintype "passive"))
      (node (ref "SW09") (pin "4") (pinfunction "4_4") (pintype "passive"))
    )
    (net (code "100") (name "Net-(IC8-BP0)") (class "Default")
      (node (ref "DISPLAY1") (pin "COM1") (pinfunction "COM1_COM1") (pintype "input"))
      (node (ref "IC8") (pin "25") (pinfunction "BP0_25") (pintype "output"))
    )
    (net (code "101") (name "Net-(IC8-BP1)") (class "Default")
      (node (ref "DISPLAY1") (pin "COM2") (pinfunction "COM2_COM2") (pintype "input"))
      (node (ref "IC8") (pin "26") (pinfunction "BP1_26") (pintype "output"))
    )
    (net (code "102") (name "Net-(IC8-BP2)") (class "Default")
      (node (ref "DISPLAY1") (pin "COM3") (pinfunction "COM3_COM3") (pintype "input"))
      (node (ref "IC8") (pin "27") (pinfunction "BP2_27") (pintype "output"))
    )
    (net (code "103") (name "Net-(IC8-S0)") (class "Default")
      (node (ref "DISPLAY1") (pin "SEG01") (pinfunction "SEG01_SEG01") (pintype "input"))
      (node (ref "IC8") (pin "29") (pinfunction "S0_29") (pintype "output"))
    )
    (net (code "104") (name "Net-(IC8-S1)") (class "Default")
      (node (ref "DISPLAY1") (pin "SEG02") (pinfunction "SEG02_SEG02") (pintype "input"))
      (node (ref "IC8") (pin "30") (pinfunction "S1_30") (pintype "output"))
    )
    (net (code "105") (name "Net-(IC8-S2)") (class "Default")
      (node (ref "DISPLAY1") (pin "SEG03") (pinfunction "SEG03_SEG03") (pintype "input"))
      (node (ref "IC8") (pin "31") (pinfunction "S2_31") (pintype "output"))
    )
    (net (code "106") (name "Net-(IC8-S3)") (class "Default")
      (node (ref "DISPLAY1") (pin "SEG04") (pinfunction "SEG04_SEG04") (pintype "input"))
      (node (ref "IC8") (pin "32") (pinfunction "S3_32") (pintype "output"))
    )
    (net (code "107") (name "Net-(IC8-S4)") (class "Default")
      (node (ref "DISPLAY1") (pin "SEG05") (pinfunction "SEG05_SEG05") (pintype "input"))
      (node (ref "IC8") (pin "34") (pinfunction "S4_34") (pintype "output"))
    )
    (net (code "108") (name "Net-(IC8-S5)") (class "Default")
      (node (ref "DISPLAY1") (pin "SEG06") (pinfunction "SEG06_SEG06") (pintype "input"))
      (node (ref "IC8") (pin "35") (pinfunction "S5_35") (pintype "output"))
    )
    (net (code "109") (name "Net-(IC8-S6)") (class "Default")
      (node (ref "DISPLAY1") (pin "SEG07") (pinfunction "SEG07_SEG07") (pintype "input"))
      (node (ref "IC8") (pin "36") (pinfunction "S6_36") (pintype "output"))
    )
    (net (code "110") (name "Net-(IC8-S7)") (class "Default")
      (node (ref "DISPLAY1") (pin "SEG08") (pinfunction "SEG08_SEG08") (pintype "input"))
      (node (ref "IC8") (pin "37") (pinfunction "S7_37") (pintype "output"))
    )
    (net (code "111") (name "Net-(IC8-S8)") (class "Default")
      (node (ref "DISPLAY1") (pin "SEG09") (pinfunction "SEG09_SEG09") (pintype "input"))
      (node (ref "IC8") (pin "38") (pinfunction "S8_38") (pintype "output"))
    )
    (net (code "112") (name "Net-(IC8-S9)") (class "Default")
      (node (ref "DISPLAY1") (pin "SEG10") (pinfunction "SEG10_SEG10") (pintype "input"))
      (node (ref "IC8") (pin "39") (pinfunction "S9_39") (pintype "output"))
    )
    (net (code "113") (name "Net-(IC8-S10)") (class "Default")
      (node (ref "DISPLAY1") (pin "SEG11") (pinfunction "SEG11_SEG11") (pintype "input"))
      (node (ref "IC8") (pin "40") (pinfunction "S10_40") (pintype "output"))
    )
    (net (code "114") (name "Net-(IC8-S11)") (class "Default")
      (node (ref "DISPLAY1") (pin "SEG12") (pinfunction "SEG12_SEG12") (pintype "input"))
      (node (ref "IC8") (pin "41") (pinfunction "S11_41") (pintype "output"))
    )
    (net (code "115") (name "Net-(IC8-S12)") (class "Default")
      (node (ref "DISPLAY1") (pin "SEG13") (pinfunction "SEG13_SEG13") (pintype "input"))
      (node (ref "IC8") (pin "42") (pinfunction "S12_42") (pintype "output"))
    )
    (net (code "116") (name "Net-(IC8-S13)") (class "Default")
      (node (ref "DISPLAY1") (pin "SEG14") (pinfunction "SEG14_SEG14") (pintype "input"))
      (node (ref "IC8") (pin "43") (pinfunction "S13_43") (pintype "output"))
    )
    (net (code "117") (name "Net-(IC8-S14)") (class "Default")
      (node (ref "DISPLAY1") (pin "SEG15") (pinfunction "SEG15_SEG15") (pintype "input"))
      (node (ref "IC8") (pin "44") (pinfunction "S14_44") (pintype "output"))
    )
    (net (code "118") (name "Net-(IC8-S15)") (class "Default")
      (node (ref "DISPLAY1") (pin "SEG16") (pinfunction "SEG16_SEG16") (pintype "input"))
      (node (ref "IC8") (pin "45") (pinfunction "S15_45") (pintype "output"))
    )
    (net (code "119") (name "Net-(IC8-S16)") (class "Default")
      (node (ref "DISPLAY1") (pin "SEG17") (pinfunction "SEG17_SEG17") (pintype "input"))
      (node (ref "IC8") (pin "46") (pinfunction "S16_46") (pintype "output"))
    )
    (net (code "120") (name "Net-(IC8-S17)") (class "Default")
      (node (ref "DISPLAY1") (pin "SEG18") (pinfunction "SEG18_SEG18") (pintype "input"))
      (node (ref "IC8") (pin "47") (pinfunction "S17_47") (pintype "output"))
    )
    (net (code "121") (name "Net-(IC8-S18)") (class "Default")
      (node (ref "DISPLAY1") (pin "SEG19") (pinfunction "SEG19_SEG19") (pintype "input"))
      (node (ref "IC8") (pin "49") (pinfunction "S18_49") (pintype "output"))
    )
    (net (code "122") (name "Net-(IC8-S19)") (class "Default")
      (node (ref "DISPLAY1") (pin "SEG20") (pinfunction "SEG20_SEG20") (pintype "input"))
      (node (ref "IC8") (pin "50") (pinfunction "S19_50") (pintype "output"))
    )
    (net (code "123") (name "Net-(IC8-S20)") (class "Default")
      (node (ref "DISPLAY1") (pin "SEG21") (pinfunction "SEG21_SEG21") (pintype "input"))
      (node (ref "IC8") (pin "51") (pinfunction "S20_51") (pintype "output"))
    )
    (net (code "124") (name "Net-(IC8-S21)") (class "Default")
      (node (ref "DISPLAY1") (pin "SEG22") (pinfunction "SEG22_SEG22") (pintype "input"))
      (node (ref "IC8") (pin "52") (pinfunction "S21_52") (pintype "output"))
    )
    (net (code "125") (name "Net-(IC8-S22)") (class "Default")
      (node (ref "DISPLAY1") (pin "SEG23") (pinfunction "SEG23_SEG23") (pintype "input"))
      (node (ref "IC8") (pin "53") (pinfunction "S22_53") (pintype "output"))
    )
    (net (code "126") (name "Net-(IC8-S23)") (class "Default")
      (node (ref "DISPLAY1") (pin "SEG24") (pinfunction "SEG24_SEG24") (pintype "input"))
      (node (ref "IC8") (pin "54") (pinfunction "S23_54") (pintype "output"))
    )
    (net (code "127") (name "Net-(IC8-S24)") (class "Default")
      (node (ref "DISPLAY1") (pin "SEG25") (pinfunction "SEG25_SEG25") (pintype "input"))
      (node (ref "IC8") (pin "55") (pinfunction "S24_55") (pintype "output"))
    )
    (net (code "128") (name "Net-(IC8-S25)") (class "Default")
      (node (ref "DISPLAY1") (pin "SEG26") (pinfunction "SEG26_SEG26") (pintype "input"))
      (node (ref "IC8") (pin "56") (pinfunction "S25_56") (pintype "output"))
    )
    (net (code "129") (name "Net-(IC8-S26)") (class "Default")
      (node (ref "DISPLAY1") (pin "SEG27") (pinfunction "SEG27_SEG27") (pintype "input"))
      (node (ref "IC8") (pin "57") (pinfunction "S26_57") (pintype "output"))
    )
    (net (code "130") (name "Net-(IC8-S27)") (class "Default")
      (node (ref "DISPLAY1") (pin "SEG28") (pinfunction "SEG28_SEG28") (pintype "input"))
      (node (ref "IC8") (pin "58") (pinfunction "S27_58") (pintype "output"))
    )
    (net (code "131") (name "Net-(IC8-S28)") (class "Default")
      (node (ref "DISPLAY1") (pin "SEG29") (pinfunction "SEG29_SEG29") (pintype "input"))
      (node (ref "IC8") (pin "59") (pinfunction "S28_59") (pintype "output"))
    )
    (net (code "132") (name "Net-(IC8-S29)") (class "Default")
      (node (ref "DISPLAY1") (pin "SEG30") (pinfunction "SEG30_SEG30") (pintype "input"))
      (node (ref "IC8") (pin "60") (pinfunction "S29_60") (pintype "output"))
    )
    (net (code "133") (name "Net-(IC8-S30)") (class "Default")
      (node (ref "DISPLAY1") (pin "SEG31") (pinfunction "SEG31_SEG31") (pintype "input"))
      (node (ref "IC8") (pin "61") (pinfunction "S30_61") (pintype "output"))
    )
    (net (code "134") (name "Net-(IC8-S31)") (class "Default")
      (node (ref "DISPLAY1") (pin "SEG32") (pinfunction "SEG32_SEG32") (pintype "input"))
      (node (ref "IC8") (pin "62") (pinfunction "S31_62") (pintype "output"))
    )
    (net (code "135") (name "Net-(IC8-S32)") (class "Default")
      (node (ref "DISPLAY1") (pin "SEG33") (pinfunction "SEG33_SEG33") (pintype "input"))
      (node (ref "IC8") (pin "63") (pinfunction "S32_63") (pintype "output"))
    )
    (net (code "136") (name "Net-(IC8-VLCD)") (class "Default")
      (node (ref "IC8") (pin "21") (pinfunction "VLCD_21") (pintype "power_in"))
      (node (ref "R30") (pin "2") (pinfunction "2_2") (pintype "passive"))
    )
    (net (code "137") (name "Net-(IC9-RH)") (class "Default")
      (node (ref "IC9") (pin "7") (pinfunction "RH_7") (pintype "bidirectional"))
      (node (ref "R28") (pin "1") (pinfunction "1_1") (pintype "passive"))
    )
    (net (code "138") (name "Net-(R1-Pad1)") (class "Default")
      (node (ref "R1") (pin "1") (pinfunction "1_1") (pintype "passive"))
      (node (ref "T6") (pin "B") (pinfunction "B_B") (pintype "passive"))
    )
    (net (code "139") (name "Net-(R7-Pad2)") (class "Default")
      (node (ref "R7") (pin "2") (pinfunction "2_2") (pintype "passive"))
      (node (ref "X7") (pin "3") (pinfunction "3_3") (pintype "passive"))
    )
    (net (code "140") (name "Net-(R11-Pad1)") (class "Default")
      (node (ref "R11") (pin "1") (pinfunction "1_1") (pintype "passive"))
      (node (ref "T5") (pin "B") (pinfunction "B_B") (pintype "passive"))
    )
    (net (code "141") (name "Net-(RF-POWER-S)") (class "Default")
      (node (ref "RF-POWER") (pin "2") (pinfunction "S_2") (pintype "passive"))
      (node (ref "X7") (pin "5") (pinfunction "5_5") (pintype "passive"))
    )
    (net (code "142") (name "Net-(SQUELCH-A)") (class "Default")
      (node (ref "R2") (pin "1") (pinfunction "1_1") (pintype "passive"))
      (node (ref "SQUELCH") (pin "3") (pinfunction "A_3") (pintype "passive"))
    )
    (net (code "143") (name "Net-(SQUELCH-S)") (class "Default")
      (node (ref "SQUELCH") (pin "2") (pinfunction "S_2") (pintype "passive"))
      (node (ref "X7") (pin "7") (pinfunction "7_7") (pintype "passive"))
    )
    (net (code "144") (name "Net-(SWR/CAL-S)") (class "Default")
      (node (ref "R7") (pin "1") (pinfunction "1_1") (pintype "passive"))
      (node (ref "SWR/CAL") (pin "2") (pinfunction "S_2") (pintype "passive"))
    )
    (net (code "145") (name "Net-(T1-B)") (class "Default")
      (node (ref "R12") (pin "2") (pinfunction "2_2") (pintype "passive"))
      (node (ref "T1") (pin "1") (pinfunction "B_1") (pintype "passive"))
    )
    (net (code "146") (name "Net-(T1-C)") (class "Default")
      (node (ref "T1") (pin "4") (pinfunction "C_4") (pintype "passive"))
      (node (ref "X6") (pin "3") (pinfunction "3_3") (pintype "passive"))
    )
    (net (code "147") (name "Net-(T4-B)") (class "Default")
      (node (ref "R15") (pin "1") (pinfunction "1_1") (pintype "passive"))
      (node (ref "T4") (pin "1") (pinfunction "B_1") (pintype "passive"))
    )
    (net (code "148") (name "Net-(T4-C)") (class "Default")
      (node (ref "R32") (pin "2") (pinfunction "2_2") (pintype "passive"))
      (node (ref "T4") (pin "4") (pinfunction "C_4") (pintype "passive"))
    )
    (net (code "149") (name "Net-(VOLUME-A)") (class "Default")
      (node (ref "VOLUME") (pin "3") (pinfunction "A_3") (pintype "passive"))
      (node (ref "X7") (pin "8") (pinfunction "8_8") (pintype "passive"))
    )
    (net (code "150") (name "Net-(VOLUME-E)") (class "Default")
      (node (ref "VOLUME") (pin "1") (pinfunction "E_1") (pintype "passive"))
      (node (ref "X7") (pin "9") (pinfunction "9_9") (pintype "passive"))
    )
    (net (code "151") (name "Net-(VOLUME-S)") (class "Default")
      (node (ref "VOLUME") (pin "2") (pinfunction "S_2") (pintype "passive"))
      (node (ref "X7") (pin "10") (pinfunction "10_10") (pintype "passive"))
    )
    (net (code "152") (name "Net-(X5B-S)") (class "Default")
      (node (ref "C18") (pin "1") (pinfunction "1_1") (pintype "passive"))
      (node (ref "R8") (pin "2") (pinfunction "2_2") (pintype "passive"))
      (node (ref "X5") (pin "2") (pinfunction "S_2") (pintype "passive"))
    )
    (net (code "153") (name "VCC") (class "Default")
      (node (ref "C13") (pin "2") (pinfunction "2_2") (pintype "passive"))
      (node (ref "C14") (pin "2") (pinfunction "2_2") (pintype "passive"))
      (node (ref "C17") (pin "2") (pinfunction "2_2") (pintype "passive"))
      (node (ref "C23") (pin "2") (pinfunction "2_2") (pintype "passive"))
      (node (ref "C24") (pin "2") (pinfunction "2_2") (pintype "passive"))
      (node (ref "C35") (pin "2") (pinfunction "2_2") (pintype "passive"))
      (node (ref "C4") (pin "+") (pinfunction "+_+") (pintype "passive"))
      (node (ref "D2") (pin "C") (pinfunction "C_C") (pintype "passive"))
      (node (ref "IC3") (pin "28") (pinfunction "VCC_28") (pintype "bidirectional"))
      (node (ref "IC4") (pin "2") (pinfunction "A0_2") (pintype "bidirectional"))
      (node (ref "IC4") (pin "28") (pinfunction "VCC_28") (pintype "bidirectional"))
      (node (ref "IC5") (pin "21") (pinfunction "A0_21") (pintype "input"))
      (node (ref "IC5") (pin "24") (pinfunction "VDD_24") (pintype "power_in"))
      (node (ref "IC6") (pin "24") (pinfunction "VDD_24") (pintype "power_in"))
      (node (ref "IC8") (pin "14") (pinfunction "VDD_14") (pintype "power_in"))
      (node (ref "IC9") (pin "1") (pinfunction "WP_1") (pintype "bidirectional"))
      (node (ref "IC9") (pin "8") (pinfunction "VCC_8") (pintype "power_in"))
      (node (ref "R13") (pin "1") (pinfunction "1_1") (pintype "passive"))
      (node (ref "R21") (pin "1") (pinfunction "1_1") (pintype "passive"))
      (node (ref "R22") (pin "1") (pinfunction "1_1") (pintype "passive"))
      (node (ref "R26") (pin "2") (pinfunction "2_2") (pintype "passive"))
      (node (ref "R27") (pin "2") (pinfunction "2_2") (pintype "passive"))
      (node (ref "R33") (pin "1") (pinfunction "1_1") (pintype "passive"))
      (node (ref "R9") (pin "1") (pinfunction "1_1") (pintype "passive"))
      (node (ref "X1") (pin "1") (pinfunction "1_1") (pintype "passive"))
    )
    (net (code "154") (name "VCCMEM") (class "Default")
      (node (ref "C16") (pin "2") (pinfunction "2_2") (pintype "passive"))
      (node (ref "C8") (pin "2") (pinfunction "2_2") (pintype "passive"))
      (node (ref "D1") (pin "C") (pinfunction "C_C") (pintype "passive"))
      (node (ref "IC1") (pin "21") (pinfunction "VCC_21") (pintype "power_in"))
      (node (ref "IC1") (pin "52") (pinfunction "VCC_52") (pintype "power_in"))
      (node (ref "IC7") (pin "3") (pinfunction "~{WP}_3") (pintype "input"))
      (node (ref "IC7") (pin "7") (pinfunction "~{HOLD}_7") (pintype "input"))
      (node (ref "IC7") (pin "8") (pinfunction "VCC_8") (pintype "power_in"))
      (node (ref "L1") (pin "2") (pinfunction "2_2") (pintype "passive"))
      (node (ref "X2") (pin "1") (pinfunction "S_1") (pintype "passive"))
    )
    (net (code "155") (name "unconnected-(IC1-(A8)PC0-Pad35)") (class "Default")
      (node (ref "IC1") (pin "35") (pinfunction "(A8)PC0_35") (pintype "output"))
    )
    (net (code "156") (name "unconnected-(IC1-(A9)PC1-Pad36)") (class "Default")
      (node (ref "IC1") (pin "36") (pinfunction "(A9)PC1_36") (pintype "output"))
    )
    (net (code "157") (name "unconnected-(IC1-(A10)PC2-Pad37)") (class "Default")
      (node (ref "IC1") (pin "37") (pinfunction "(A10)PC2_37") (pintype "output"))
    )
    (net (code "158") (name "unconnected-(IC1-(A13)PC5-Pad40)") (class "Default")
      (node (ref "IC1") (pin "40") (pinfunction "(A13)PC5_40") (pintype "output"))
    )
    (net (code "159") (name "unconnected-(IC1-(A14)PC6-Pad41)") (class "Default")
      (node (ref "IC1") (pin "41") (pinfunction "(A14)PC6_41") (pintype "output"))
    )
    (net (code "160") (name "unconnected-(IC1-(A15)PC7-Pad42)") (class "Default")
      (node (ref "IC1") (pin "42") (pinfunction "(A15)PC7_42") (pintype "output"))
    )
    (net (code "161") (name "unconnected-(IC1-(AD0)PA0-Pad51)") (class "Default")
      (node (ref "IC1") (pin "51") (pinfunction "(AD0)PA0_51") (pintype "bidirectional"))
    )
    (net (code "162") (name "unconnected-(IC1-(AD1)PA1-Pad50)") (class "Default")
      (node (ref "IC1") (pin "50") (pinfunction "(AD1)PA1_50") (pintype "bidirectional"))
    )
    (net (code "163") (name "unconnected-(IC1-(IC1)PD4-Pad29)") (class "Default")
      (node (ref "IC1") (pin "29") (pinfunction "(IC1)PD4_29") (pintype "bidirectional"))
    )
    (net (code "164") (name "unconnected-(IC1-(OC0)PB4-Pad14)") (class "Default")
      (node (ref "IC1") (pin "14") (pinfunction "(OC0)PB4_14") (pintype "bidirectional"))
    )
    (net (code "165") (name "unconnected-(IC1-(OC1B)PB6-Pad16)") (class "Default")
      (node (ref "IC1") (pin "16") (pinfunction "(OC1B)PB6_16") (pintype "bidirectional"))
    )
    (net (code "166") (name "unconnected-(IC1-(OC2{slash}OC1C)PB7-Pad17)") (class "Default")
      (node (ref "IC1") (pin "17") (pinfunction "(OC2/OC1C)PB7_17") (pintype "bidirectional"))
    )
    (net (code "167") (name "unconnected-(IC1-(OC3A{slash}AIN1)PE3-Pad5)") (class "Default")
      (node (ref "IC1") (pin "5") (pinfunction "(OC3A/AIN1)PE3_5") (pintype "bidirectional"))
    )
    (net (code "168") (name "unconnected-(IC1-(T1)PD6-Pad31)") (class "Default")
      (node (ref "IC1") (pin "31") (pinfunction "(T1)PD6_31") (pintype "bidirectional"))
    )
    (net (code "169") (name "unconnected-(IC1-(T2)PD7-Pad32)") (class "Default")
      (node (ref "IC1") (pin "32") (pinfunction "(T2)PD7_32") (pintype "bidirectional"))
    )
    (net (code "170") (name "unconnected-(IC1-(XCK1)PD5-Pad30)") (class "Default")
      (node (ref "IC1") (pin "30") (pinfunction "(XCK1)PD5_30") (pintype "bidirectional"))
    )
    (net (code "171") (name "unconnected-(IC1-AREF-Pad62)") (class "Default")
      (node (ref "IC1") (pin "62") (pinfunction "AREF_62") (pintype "passive"))
    )
    (net (code "172") (name "unconnected-(IC1-PEN-Pad1)") (class "Default")
      (node (ref "IC1") (pin "1") (pinfunction "PEN_1") (pintype "input"))
    )
    (net (code "173") (name "unconnected-(IC1-PF2(ADC2)-Pad59)") (class "Default")
      (node (ref "IC1") (pin "59") (pinfunction "PF2(ADC2)_59") (pintype "input"))
    )
    (net (code "174") (name "unconnected-(IC1-PF3(ADC3)-Pad58)") (class "Default")
      (node (ref "IC1") (pin "58") (pinfunction "PF3(ADC3)_58") (pintype "input"))
    )
    (net (code "175") (name "unconnected-(IC1-PF4(ADC4{slash}TCK)-Pad57)") (class "Default")
      (node (ref "IC1") (pin "57") (pinfunction "PF4(ADC4/TCK)_57") (pintype "input"))
    )
    (net (code "176") (name "unconnected-(IC1-PF5(ADC5{slash}TMS)-Pad56)") (class "Default")
      (node (ref "IC1") (pin "56") (pinfunction "PF5(ADC5/TMS)_56") (pintype "input"))
    )
    (net (code "177") (name "unconnected-(IC1-PF6(ADC6{slash}TDO)-Pad55)") (class "Default")
      (node (ref "IC1") (pin "55") (pinfunction "PF6(ADC6/TDO)_55") (pintype "input"))
    )
    (net (code "178") (name "unconnected-(IC1-PF7(ADC7{slash}TDI)-Pad54)") (class "Default")
      (node (ref "IC1") (pin "54") (pinfunction "PF7(ADC7/TDI)_54") (pintype "input"))
    )
    (net (code "179") (name "unconnected-(IC1-PG0(WR)-Pad33)") (class "Default")
      (node (ref "IC1") (pin "33") (pinfunction "PG0(WR)_33") (pintype "bidirectional"))
    )
    (net (code "180") (name "unconnected-(IC1-PG1(RD)-Pad34)") (class "Default")
      (node (ref "IC1") (pin "34") (pinfunction "PG1(RD)_34") (pintype "bidirectional"))
    )
    (net (code "181") (name "unconnected-(IC1-PG2(ALE)-Pad43)") (class "Default")
      (node (ref "IC1") (pin "43") (pinfunction "PG2(ALE)_43") (pintype "bidirectional"))
    )
    (net (code "182") (name "unconnected-(IC1-PG3(TOSC2)-Pad18)") (class "Default")
      (node (ref "IC1") (pin "18") (pinfunction "PG3(TOSC2)_18") (pintype "bidirectional"))
    )
    (net (code "183") (name "unconnected-(IC1-PG4(TOSC1)-Pad19)") (class "Default")
      (node (ref "IC1") (pin "19") (pinfunction "PG4(TOSC1)_19") (pintype "bidirectional"))
    )
    (net (code "184") (name "unconnected-(IC3-{slash}OUT12-Pad20)") (class "Default")
      (node (ref "IC3") (pin "20") (pinfunction "/OUT12_20") (pintype "bidirectional"))
    )
    (net (code "185") (name "unconnected-(IC3-{slash}OUT13-Pad21)") (class "Default")
      (node (ref "IC3") (pin "21") (pinfunction "/OUT13_21") (pintype "bidirectional"))
    )
    (net (code "186") (name "unconnected-(IC3-{slash}OUT14-Pad22)") (class "Default")
      (node (ref "IC3") (pin "22") (pinfunction "/OUT14_22") (pintype "bidirectional"))
    )
    (net (code "187") (name "unconnected-(IC3-{slash}OUT15-Pad23)") (class "Default")
      (node (ref "IC3") (pin "23") (pinfunction "/OUT15_23") (pintype "bidirectional"))
    )
    (net (code "188") (name "unconnected-(IC4-{slash}OUT12-Pad20)") (class "Default")
      (node (ref "IC4") (pin "20") (pinfunction "/OUT12_20") (pintype "bidirectional"))
    )
    (net (code "189") (name "unconnected-(IC4-{slash}OUT13-Pad21)") (class "Default")
      (node (ref "IC4") (pin "21") (pinfunction "/OUT13_21") (pintype "bidirectional"))
    )
    (net (code "190") (name "unconnected-(IC4-{slash}OUT14-Pad22)") (class "Default")
      (node (ref "IC4") (pin "22") (pinfunction "/OUT14_22") (pintype "bidirectional"))
    )
    (net (code "191") (name "unconnected-(IC4-{slash}OUT15-Pad23)") (class "Default")
      (node (ref "IC4") (pin "23") (pinfunction "/OUT15_23") (pintype "bidirectional"))
    )
    (net (code "192") (name "unconnected-(IC5-I{slash}O0.3-Pad7)") (class "Default")
      (node (ref "IC5") (pin "7") (pinfunction "I/O0.3_7") (pintype "bidirectional"))
    )
    (net (code "193") (name "unconnected-(IC5-I{slash}O0.4-Pad8)") (class "Default")
      (node (ref "IC5") (pin "8") (pinfunction "I/O0.4_8") (pintype "bidirectional"))
    )
    (net (code "194") (name "unconnected-(IC5-I{slash}O0.5-Pad9)") (class "Default")
      (node (ref "IC5") (pin "9") (pinfunction "I/O0.5_9") (pintype "bidirectional"))
    )
    (net (code "195") (name "unconnected-(IC6-I{slash}O0.7-Pad11)") (class "Default")
      (node (ref "IC6") (pin "11") (pinfunction "I/O0.7_11") (pintype "bidirectional"))
    )
    (net (code "196") (name "unconnected-(IC6-I{slash}O1.5-Pad18)") (class "Default")
      (node (ref "IC6") (pin "18") (pinfunction "I/O1.5_18") (pintype "bidirectional"))
    )
    (net (code "197") (name "unconnected-(IC6-I{slash}O1.6-Pad19)") (class "Default")
      (node (ref "IC6") (pin "19") (pinfunction "I/O1.6_19") (pintype "bidirectional"))
    )
    (net (code "198") (name "unconnected-(IC6-I{slash}O1.7-Pad20)") (class "Default")
      (node (ref "IC6") (pin "20") (pinfunction "I/O1.7_20") (pintype "bidirectional"))
    )
    (net (code "199") (name "unconnected-(IC8-BP3-Pad28)") (class "Default")
      (node (ref "IC8") (pin "28") (pinfunction "BP3_28") (pintype "output"))
    )
    (net (code "200") (name "unconnected-(IC8-CLK-Pad13)") (class "Default")
      (node (ref "IC8") (pin "13") (pinfunction "CLK_13") (pintype "bidirectional"))
    )
    (net (code "201") (name "unconnected-(IC8-S33-Pad64)") (class "Default")
      (node (ref "IC8") (pin "64") (pinfunction "S33_64") (pintype "output"))
    )
    (net (code "202") (name "unconnected-(IC8-S34-Pad2)") (class "Default")
      (node (ref "IC8") (pin "2") (pinfunction "S34_2") (pintype "output"))
    )
    (net (code "203") (name "unconnected-(IC8-S35-Pad3)") (class "Default")
      (node (ref "IC8") (pin "3") (pinfunction "S35_3") (pintype "output"))
    )
    (net (code "204") (name "unconnected-(IC8-S36-Pad4)") (class "Default")
      (node (ref "IC8") (pin "4") (pinfunction "S36_4") (pintype "output"))
    )
    (net (code "205") (name "unconnected-(IC8-S37-Pad5)") (class "Default")
      (node (ref "IC8") (pin "5") (pinfunction "S37_5") (pintype "output"))
    )
    (net (code "206") (name "unconnected-(IC8-S38-Pad6)") (class "Default")
      (node (ref "IC8") (pin "6") (pinfunction "S38_6") (pintype "output"))
    )
    (net (code "207") (name "unconnected-(IC8-S39-Pad7)") (class "Default")
      (node (ref "IC8") (pin "7") (pinfunction "S39_7") (pintype "output"))
    )
    (net (code "208") (name "unconnected-(IC8-SYNC-Pad12)") (class "Default")
      (node (ref "IC8") (pin "12") (pinfunction "SYNC_12") (pintype "bidirectional"))
    )
    (net (code "209") (name "unconnected-(RF-POWER-A-Pad3)") (class "Default")
      (node (ref "RF-POWER") (pin "3") (pinfunction "A_3") (pintype "passive"))
    )
  )
)
